# BMS_Slave_v2.net
KiCad netlist of a schematic drawn in EAGLE
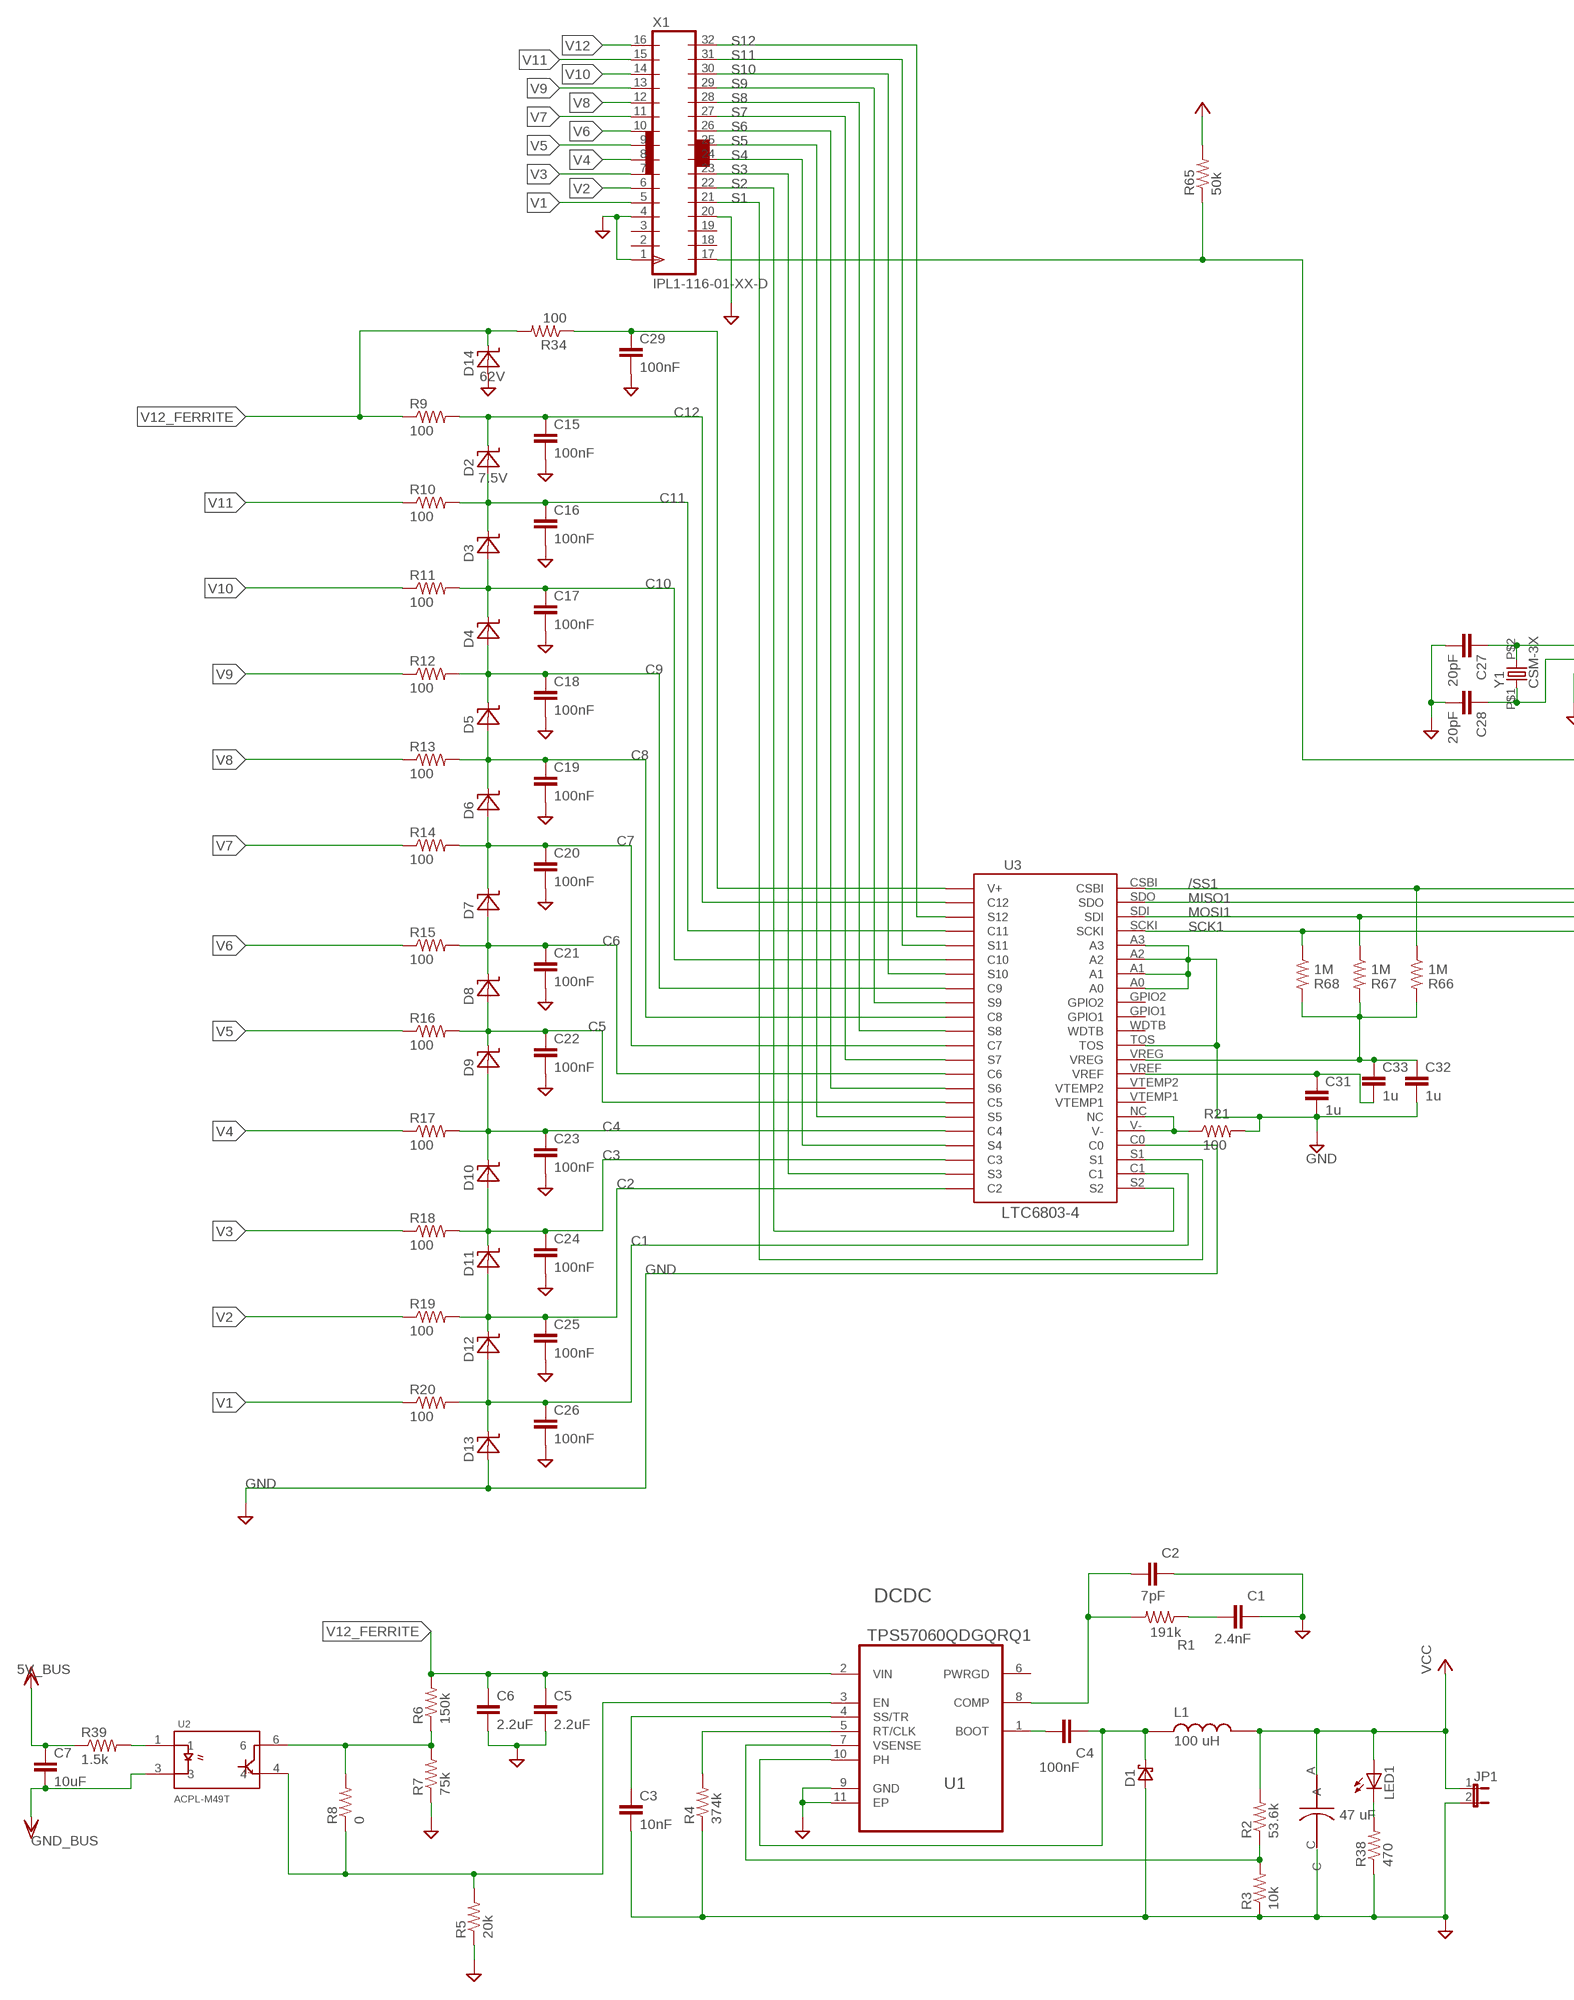
[diagram p0: schematic, sheet 1, part 1 of 2]
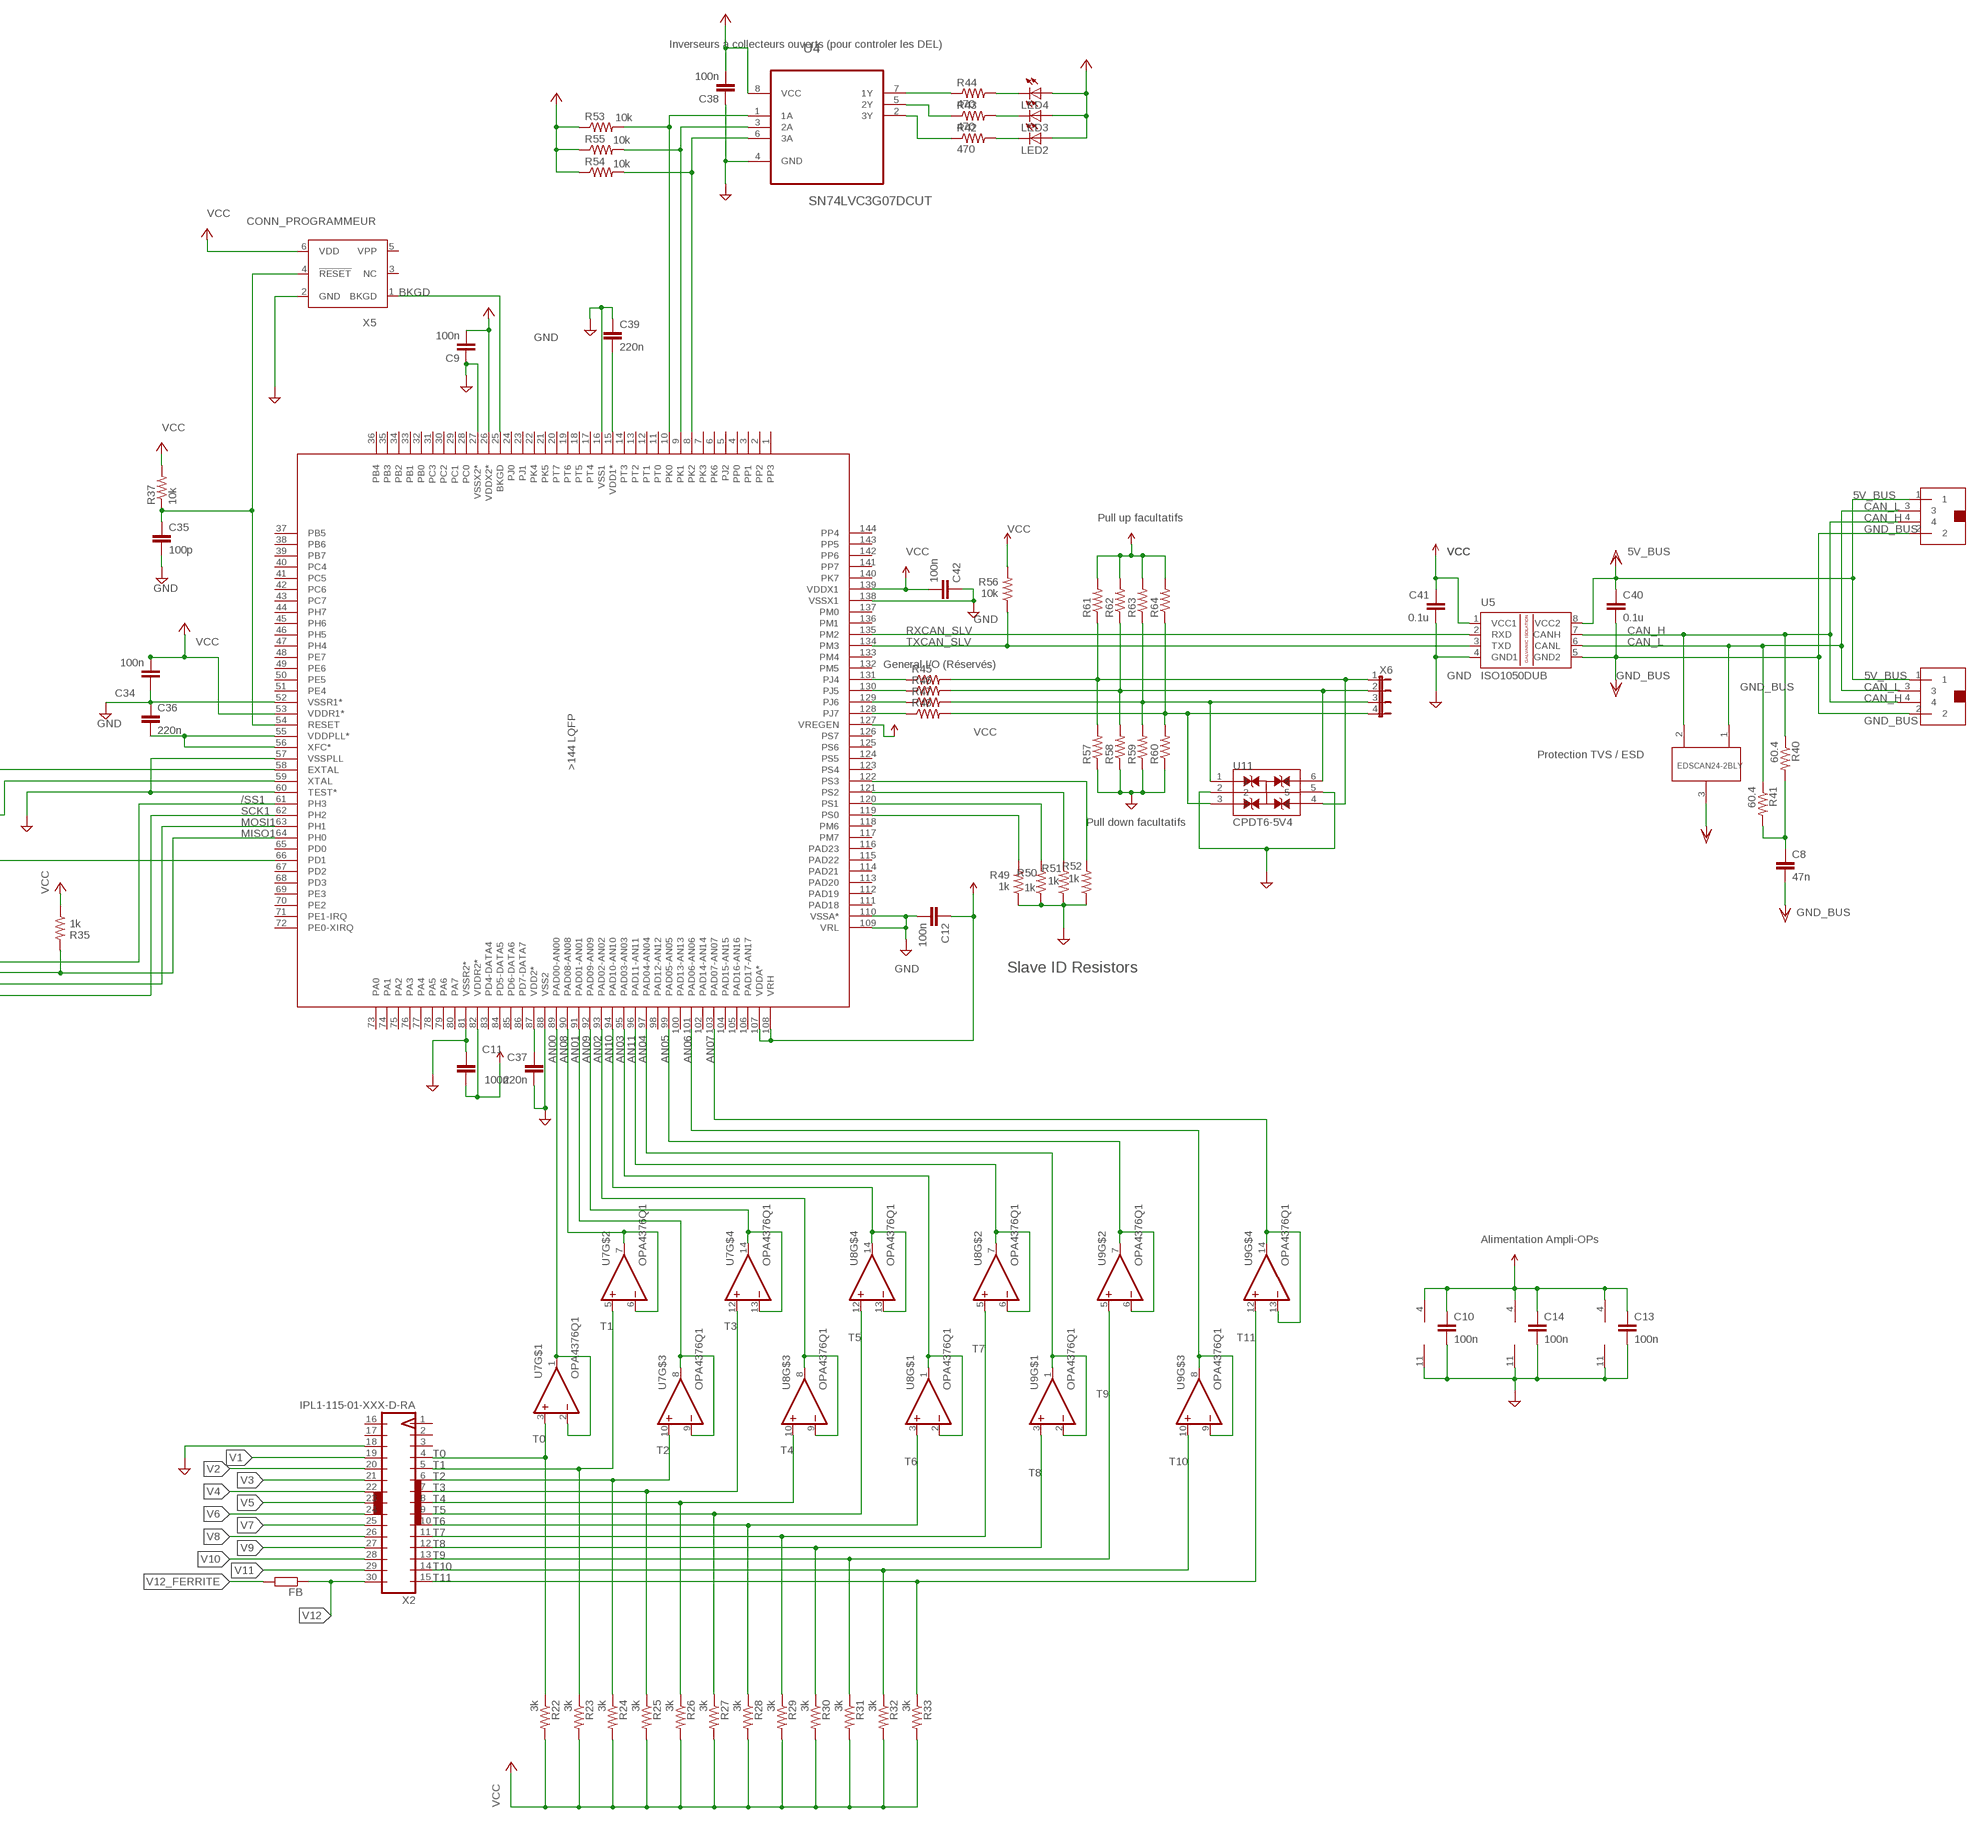
[diagram p1: schematic, sheet 1, part 2 of 2]

(export (version "E")
  (design (tool "Eeschema 10.0.6"))
  (components
    (comp (ref "C1")
      (value "2.4nF")
      (footprint "eagle-import:C0603")
      (libsource (lib "eagle-import") (part "CC0603"))
    )
    (comp (ref "C2")
      (value "7pF")
      (footprint "eagle-import:C0603")
      (libsource (lib "eagle-import") (part "CC0603"))
    )
    (comp (ref "C3")
      (value "10nF")
      (footprint "eagle-import:C0603")
      (libsource (lib "eagle-import") (part "CC0603"))
    )
    (comp (ref "C4")
      (value "100nF")
      (footprint "eagle-import:C0603")
      (libsource (lib "eagle-import") (part "CC0603"))
    )
    (comp (ref "C5")
      (value "2.2uF")
      (footprint "eagle-import:C3225")
      (libsource (lib "eagle-import") (part "resistor_C-EUC3225"))
    )
    (comp (ref "C6")
      (value "2.2uF")
      (footprint "eagle-import:C3225")
      (libsource (lib "eagle-import") (part "resistor_C-EUC3225"))
    )
    (comp (ref "C7")
      (value "10uF")
      (footprint "eagle-import:C0603")
      (libsource (lib "eagle-import") (part "CC0603"))
    )
    (comp (ref "C8")
      (value "47n")
      (footprint "eagle-import:C0603")
      (libsource (lib "eagle-import") (part "C-EUC0603"))
    )
    (comp (ref "C9")
      (value "100n")
      (footprint "eagle-import:C0603")
      (libsource (lib "eagle-import") (part "C-EUC0603"))
    )
    (comp (ref "C10")
      (value "100n")
      (footprint "eagle-import:C0603")
      (libsource (lib "eagle-import") (part "C-EUC0603"))
    )
    (comp (ref "C11")
      (value "100n")
      (footprint "eagle-import:C0603")
      (libsource (lib "eagle-import") (part "CC0603"))
    )
    (comp (ref "C12")
      (value "100n")
      (footprint "eagle-import:C0603")
      (libsource (lib "eagle-import") (part "C-EUC0603"))
    )
    (comp (ref "C13")
      (value "100n")
      (footprint "eagle-import:C0603")
      (libsource (lib "eagle-import") (part "C-EUC0603"))
    )
    (comp (ref "C14")
      (value "100n")
      (footprint "eagle-import:C0603")
      (libsource (lib "eagle-import") (part "C-EUC0603"))
    )
    (comp (ref "C15")
      (value "100nF")
      (footprint "eagle-import:C0603")
      (libsource (lib "eagle-import") (part "CC0603"))
    )
    (comp (ref "C16")
      (value "100nF")
      (footprint "eagle-import:C0603")
      (libsource (lib "eagle-import") (part "CC0603"))
    )
    (comp (ref "C17")
      (value "100nF")
      (footprint "eagle-import:C0603")
      (libsource (lib "eagle-import") (part "CC0603"))
    )
    (comp (ref "C18")
      (value "100nF")
      (footprint "eagle-import:C0603")
      (libsource (lib "eagle-import") (part "CC0603"))
    )
    (comp (ref "C19")
      (value "100nF")
      (footprint "eagle-import:C0603")
      (libsource (lib "eagle-import") (part "CC0603"))
    )
    (comp (ref "C20")
      (value "100nF")
      (footprint "eagle-import:C0603")
      (libsource (lib "eagle-import") (part "CC0603"))
    )
    (comp (ref "C21")
      (value "100nF")
      (footprint "eagle-import:C0603")
      (libsource (lib "eagle-import") (part "CC0603"))
    )
    (comp (ref "C22")
      (value "100nF")
      (footprint "eagle-import:C0603")
      (libsource (lib "eagle-import") (part "CC0603"))
    )
    (comp (ref "C23")
      (value "100nF")
      (footprint "eagle-import:C0603")
      (libsource (lib "eagle-import") (part "CC0603"))
    )
    (comp (ref "C24")
      (value "100nF")
      (footprint "eagle-import:C0603")
      (libsource (lib "eagle-import") (part "CC0603"))
    )
    (comp (ref "C25")
      (value "100nF")
      (footprint "eagle-import:C0603")
      (libsource (lib "eagle-import") (part "CC0603"))
    )
    (comp (ref "C26")
      (value "100nF")
      (footprint "eagle-import:C0603")
      (libsource (lib "eagle-import") (part "CC0603"))
    )
    (comp (ref "C27")
      (value "20pF")
      (footprint "eagle-import:C0603")
      (libsource (lib "eagle-import") (part "C-EUC0603"))
    )
    (comp (ref "C28")
      (value "20pF")
      (footprint "eagle-import:C0603")
      (libsource (lib "eagle-import") (part "C-EUC0603"))
    )
    (comp (ref "C29")
      (value "100nF")
      (footprint "eagle-import:C0603")
      (libsource (lib "eagle-import") (part "CC0603"))
    )
    (comp (ref "C31")
      (value "1u")
      (footprint "eagle-import:C0603")
      (libsource (lib "eagle-import") (part "CC0603"))
    )
    (comp (ref "C32")
      (value "1u")
      (footprint "eagle-import:C0603")
      (libsource (lib "eagle-import") (part "CC0603"))
    )
    (comp (ref "C33")
      (value "1u")
      (footprint "eagle-import:C0603")
      (libsource (lib "eagle-import") (part "CC0603"))
    )
    (comp (ref "C34")
      (value "100n")
      (footprint "eagle-import:C0603")
      (libsource (lib "eagle-import") (part "CC0603"))
    )
    (comp (ref "C35")
      (value "100p")
      (footprint "eagle-import:C0603")
      (libsource (lib "eagle-import") (part "CC0603"))
    )
    (comp (ref "C36")
      (value "220n")
      (footprint "eagle-import:C0603")
      (libsource (lib "eagle-import") (part "CC0603"))
    )
    (comp (ref "C37")
      (value "220n")
      (footprint "eagle-import:C0603")
      (libsource (lib "eagle-import") (part "C-EUC0603"))
    )
    (comp (ref "C38")
      (value "100n")
      (footprint "eagle-import:C0603")
      (libsource (lib "eagle-import") (part "C-EUC0603"))
    )
    (comp (ref "C39")
      (value "220n")
      (footprint "eagle-import:C0603")
      (libsource (lib "eagle-import") (part "C-EUC0603"))
    )
    (comp (ref "C40")
      (value "0.1u")
      (footprint "eagle-import:C0603")
      (libsource (lib "eagle-import") (part "C-EUC0603"))
    )
    (comp (ref "C41")
      (value "0.1u")
      (footprint "eagle-import:C0603")
      (libsource (lib "eagle-import") (part "C-EUC0603"))
    )
    (comp (ref "C42")
      (value "100n")
      (footprint "eagle-import:C0603")
      (libsource (lib "eagle-import") (part "C-EUC0603"))
    )
    (comp (ref "C43")
      (value "47 uF")
      (footprint "eagle-import:APXE_CONDENSATEUR")
      (libsource (lib "eagle-import") (part "APXE_47_COND"))
    )
    (comp (ref "D1")
      (value "BYS12-90GENERIC")
      (footprint "eagle-import:DO214AC_ZENER")
      (libsource (lib "eagle-import") (part "BYS12-90GENERIC"))
    )
    (comp (ref "D2")
      (value "DIODE_ZENER")
      (footprint "eagle-import:SOD123")
      (libsource (lib "eagle-import") (part "DIODE_ZENER"))
    )
    (comp (ref "D3")
      (value "DIODE_ZENER")
      (footprint "eagle-import:SOD123")
      (libsource (lib "eagle-import") (part "DIODE_ZENER"))
    )
    (comp (ref "D4")
      (value "DIODE_ZENER")
      (footprint "eagle-import:SOD123")
      (libsource (lib "eagle-import") (part "DIODE_ZENER"))
    )
    (comp (ref "D5")
      (value "DIODE_ZENER")
      (footprint "eagle-import:SOD123")
      (libsource (lib "eagle-import") (part "DIODE_ZENER"))
    )
    (comp (ref "D6")
      (value "DIODE_ZENER")
      (footprint "eagle-import:SOD123")
      (libsource (lib "eagle-import") (part "DIODE_ZENER"))
    )
    (comp (ref "D7")
      (value "DIODE_ZENER")
      (footprint "eagle-import:SOD123")
      (libsource (lib "eagle-import") (part "DIODE_ZENER"))
    )
    (comp (ref "D8")
      (value "DIODE_ZENER")
      (footprint "eagle-import:SOD123")
      (libsource (lib "eagle-import") (part "DIODE_ZENER"))
    )
    (comp (ref "D9")
      (value "DIODE_ZENER")
      (footprint "eagle-import:SOD123")
      (libsource (lib "eagle-import") (part "DIODE_ZENER"))
    )
    (comp (ref "D10")
      (value "DIODE_ZENER")
      (footprint "eagle-import:SOD123")
      (libsource (lib "eagle-import") (part "DIODE_ZENER"))
    )
    (comp (ref "D11")
      (value "DIODE_ZENER")
      (footprint "eagle-import:SOD123")
      (libsource (lib "eagle-import") (part "DIODE_ZENER"))
    )
    (comp (ref "D12")
      (value "DIODE_ZENER")
      (footprint "eagle-import:SOD123")
      (libsource (lib "eagle-import") (part "DIODE_ZENER"))
    )
    (comp (ref "D13")
      (value "DIODE_ZENER")
      (footprint "eagle-import:SOD123")
      (libsource (lib "eagle-import") (part "DIODE_ZENER"))
    )
    (comp (ref "D14")
      (value "DIODE_ZENER")
      (footprint "eagle-import:SOD123")
      (libsource (lib "eagle-import") (part "DIODE_ZENER"))
    )
    (comp (ref "FB")
      (value "R-EU_R0805")
      (footprint "eagle-import:R0805")
      (libsource (lib "eagle-import") (part "R-EU_R0805"))
    )
    (comp (ref "JP1")
      (value "JP1E")
      (footprint "eagle-import:JP1")
      (libsource (lib "eagle-import") (part "JP1E"))
    )
    (comp (ref "L1")
      (value "100 uH")
      (footprint "eagle-import:VLP8040T-101M")
      (libsource (lib "eagle-import") (part "VLP8040T-101M"))
    )
    (comp (ref "LED1")
      (value "LED")
      (footprint "eagle-import:1206_LED")
      (libsource (lib "eagle-import") (part "LED"))
    )
    (comp (ref "LED2")
      (value "LED")
      (footprint "eagle-import:1206_LED")
      (libsource (lib "eagle-import") (part "ELE4000_BMS_LED"))
    )
    (comp (ref "LED3")
      (value "LED")
      (footprint "eagle-import:1206_LED")
      (libsource (lib "eagle-import") (part "ELE4000_BMS_LED"))
    )
    (comp (ref "LED4")
      (value "LED")
      (footprint "eagle-import:1206_LED")
      (libsource (lib "eagle-import") (part "ELE4000_BMS_LED"))
    )
    (comp (ref "R1")
      (value "191k")
      (footprint "eagle-import:R0603")
      (libsource (lib "eagle-import") (part "resistor_R-US_R0603"))
    )
    (comp (ref "R2")
      (value "53.6k")
      (footprint "eagle-import:R0603")
      (libsource (lib "eagle-import") (part "resistor_R-US_R0603"))
    )
    (comp (ref "R3")
      (value "10k")
      (footprint "eagle-import:R0603")
      (libsource (lib "eagle-import") (part "resistor_R-US_R0603"))
    )
    (comp (ref "R4")
      (value "374k")
      (footprint "eagle-import:R0603")
      (libsource (lib "eagle-import") (part "resistor_R-US_R0603"))
    )
    (comp (ref "R5")
      (value "20k")
      (footprint "eagle-import:R0603")
      (libsource (lib "eagle-import") (part "resistor_R-US_R0603"))
    )
    (comp (ref "R6")
      (value "150k")
      (footprint "eagle-import:R0603")
      (libsource (lib "eagle-import") (part "resistor_R-US_R0603"))
    )
    (comp (ref "R7")
      (value "75k")
      (footprint "eagle-import:R0603")
      (libsource (lib "eagle-import") (part "resistor_R-US_R0603"))
    )
    (comp (ref "R8")
      (value "0")
      (footprint "eagle-import:R0603")
      (libsource (lib "eagle-import") (part "resistor_R-US_R0603"))
    )
    (comp (ref "R9")
      (value "100")
      (footprint "eagle-import:R0603")
      (libsource (lib "eagle-import") (part "resistor_R-US_R0603"))
    )
    (comp (ref "R10")
      (value "100")
      (footprint "eagle-import:R0603")
      (libsource (lib "eagle-import") (part "resistor_R-US_R0603"))
    )
    (comp (ref "R11")
      (value "100")
      (footprint "eagle-import:R0603")
      (libsource (lib "eagle-import") (part "resistor_R-US_R0603"))
    )
    (comp (ref "R12")
      (value "100")
      (footprint "eagle-import:R0603")
      (libsource (lib "eagle-import") (part "resistor_R-US_R0603"))
    )
    (comp (ref "R13")
      (value "100")
      (footprint "eagle-import:R0603")
      (libsource (lib "eagle-import") (part "resistor_R-US_R0603"))
    )
    (comp (ref "R14")
      (value "100")
      (footprint "eagle-import:R0603")
      (libsource (lib "eagle-import") (part "resistor_R-US_R0603"))
    )
    (comp (ref "R15")
      (value "100")
      (footprint "eagle-import:R0603")
      (libsource (lib "eagle-import") (part "resistor_R-US_R0603"))
    )
    (comp (ref "R16")
      (value "100")
      (footprint "eagle-import:R0603")
      (libsource (lib "eagle-import") (part "resistor_R-US_R0603"))
    )
    (comp (ref "R17")
      (value "100")
      (footprint "eagle-import:R0603")
      (libsource (lib "eagle-import") (part "resistor_R-US_R0603"))
    )
    (comp (ref "R18")
      (value "100")
      (footprint "eagle-import:R0603")
      (libsource (lib "eagle-import") (part "resistor_R-US_R0603"))
    )
    (comp (ref "R19")
      (value "100")
      (footprint "eagle-import:R0603")
      (libsource (lib "eagle-import") (part "resistor_R-US_R0603"))
    )
    (comp (ref "R20")
      (value "100")
      (footprint "eagle-import:R0603")
      (libsource (lib "eagle-import") (part "resistor_R-US_R0603"))
    )
    (comp (ref "R21")
      (value "100")
      (footprint "eagle-import:R0603")
      (libsource (lib "eagle-import") (part "resistor_R-US_R0603"))
    )
    (comp (ref "R22")
      (value "3k")
      (footprint "eagle-import:R0603")
      (libsource (lib "eagle-import") (part "R-US_R0603"))
    )
    (comp (ref "R23")
      (value "3k")
      (footprint "eagle-import:R0603")
      (libsource (lib "eagle-import") (part "R-US_R0603"))
    )
    (comp (ref "R24")
      (value "3k")
      (footprint "eagle-import:R0603")
      (libsource (lib "eagle-import") (part "R-US_R0603"))
    )
    (comp (ref "R25")
      (value "3k")
      (footprint "eagle-import:R0603")
      (libsource (lib "eagle-import") (part "R-US_R0603"))
    )
    (comp (ref "R26")
      (value "3k")
      (footprint "eagle-import:R0603")
      (libsource (lib "eagle-import") (part "R-US_R0603"))
    )
    (comp (ref "R27")
      (value "3k")
      (footprint "eagle-import:R0603")
      (libsource (lib "eagle-import") (part "R-US_R0603"))
    )
    (comp (ref "R28")
      (value "3k")
      (footprint "eagle-import:R0603")
      (libsource (lib "eagle-import") (part "R-US_R0603"))
    )
    (comp (ref "R29")
      (value "3k")
      (footprint "eagle-import:R0603")
      (libsource (lib "eagle-import") (part "R-US_R0603"))
    )
    (comp (ref "R30")
      (value "3k")
      (footprint "eagle-import:R0603")
      (libsource (lib "eagle-import") (part "R-US_R0603"))
    )
    (comp (ref "R31")
      (value "3k")
      (footprint "eagle-import:R0603")
      (libsource (lib "eagle-import") (part "R-US_R0603"))
    )
    (comp (ref "R32")
      (value "3k")
      (footprint "eagle-import:R0603")
      (libsource (lib "eagle-import") (part "R-US_R0603"))
    )
    (comp (ref "R33")
      (value "3k")
      (footprint "eagle-import:R0603")
      (libsource (lib "eagle-import") (part "R-US_R0603"))
    )
    (comp (ref "R34")
      (value "100")
      (footprint "eagle-import:R0603")
      (libsource (lib "eagle-import") (part "resistor_R-US_R0603"))
    )
    (comp (ref "R35")
      (value "1k")
      (footprint "eagle-import:R0603")
      (libsource (lib "eagle-import") (part "resistor_R-US_R0603"))
    )
    (comp (ref "R37")
      (value "10k")
      (footprint "eagle-import:R0603")
      (libsource (lib "eagle-import") (part "resistor_R-US_R0603"))
    )
    (comp (ref "R38")
      (value "470")
      (footprint "eagle-import:R0603")
      (libsource (lib "eagle-import") (part "R-US_R0603"))
    )
    (comp (ref "R39")
      (value "1.5k")
      (footprint "eagle-import:R0603")
      (libsource (lib "eagle-import") (part "resistor_R-US_R0603"))
    )
    (comp (ref "R40")
      (value "60.4")
      (footprint "eagle-import:R0603")
      (libsource (lib "eagle-import") (part "R-US_R0603"))
    )
    (comp (ref "R41")
      (value "60.4")
      (footprint "eagle-import:R0603")
      (libsource (lib "eagle-import") (part "R-US_R0603"))
    )
    (comp (ref "R42")
      (value "470")
      (footprint "eagle-import:R0603")
      (libsource (lib "eagle-import") (part "resistor_R-US_R0603"))
    )
    (comp (ref "R43")
      (value "470")
      (footprint "eagle-import:R0603")
      (libsource (lib "eagle-import") (part "resistor_R-US_R0603"))
    )
    (comp (ref "R44")
      (value "470")
      (footprint "eagle-import:R0603")
      (libsource (lib "eagle-import") (part "resistor_R-US_R0603"))
    )
    (comp (ref "R45")
      (value "R-US_R0603")
      (footprint "eagle-import:R0603")
      (libsource (lib "eagle-import") (part "R-US_R0603"))
    )
    (comp (ref "R46")
      (value "R-US_R0603")
      (footprint "eagle-import:R0603")
      (libsource (lib "eagle-import") (part "R-US_R0603"))
    )
    (comp (ref "R47")
      (value "R-US_R0603")
      (footprint "eagle-import:R0603")
      (libsource (lib "eagle-import") (part "R-US_R0603"))
    )
    (comp (ref "R48")
      (value "R-US_R0603")
      (footprint "eagle-import:R0603")
      (libsource (lib "eagle-import") (part "R-US_R0603"))
    )
    (comp (ref "R49")
      (value "1k")
      (footprint "eagle-import:R0603")
      (libsource (lib "eagle-import") (part "resistor_R-US_R0603"))
    )
    (comp (ref "R50")
      (value "1k")
      (footprint "eagle-import:R0603")
      (libsource (lib "eagle-import") (part "resistor_R-US_R0603"))
    )
    (comp (ref "R51")
      (value "1k")
      (footprint "eagle-import:R0603")
      (libsource (lib "eagle-import") (part "resistor_R-US_R0603"))
    )
    (comp (ref "R52")
      (value "1k")
      (footprint "eagle-import:R0603")
      (libsource (lib "eagle-import") (part "resistor_R-US_R0603"))
    )
    (comp (ref "R53")
      (value "10k")
      (footprint "eagle-import:R0603")
      (libsource (lib "eagle-import") (part "resistor_R-US_R0603"))
    )
    (comp (ref "R54")
      (value "10k")
      (footprint "eagle-import:R0603")
      (libsource (lib "eagle-import") (part "resistor_R-US_R0603"))
    )
    (comp (ref "R55")
      (value "10k")
      (footprint "eagle-import:R0603")
      (libsource (lib "eagle-import") (part "resistor_R-US_R0603"))
    )
    (comp (ref "R56")
      (value "10k")
      (footprint "eagle-import:R0603")
      (libsource (lib "eagle-import") (part "resistor_R-US_R0603"))
    )
    (comp (ref "R57")
      (value "R-US_R0603")
      (footprint "eagle-import:R0603")
      (libsource (lib "eagle-import") (part "R-US_R0603"))
    )
    (comp (ref "R58")
      (value "R-US_R0603")
      (footprint "eagle-import:R0603")
      (libsource (lib "eagle-import") (part "R-US_R0603"))
    )
    (comp (ref "R59")
      (value "R-US_R0603")
      (footprint "eagle-import:R0603")
      (libsource (lib "eagle-import") (part "R-US_R0603"))
    )
    (comp (ref "R60")
      (value "R-US_R0603")
      (footprint "eagle-import:R0603")
      (libsource (lib "eagle-import") (part "R-US_R0603"))
    )
    (comp (ref "R61")
      (value "R-US_R0603")
      (footprint "eagle-import:R0603")
      (libsource (lib "eagle-import") (part "R-US_R0603"))
    )
    (comp (ref "R62")
      (value "R-US_R0603")
      (footprint "eagle-import:R0603")
      (libsource (lib "eagle-import") (part "R-US_R0603"))
    )
    (comp (ref "R63")
      (value "R-US_R0603")
      (footprint "eagle-import:R0603")
      (libsource (lib "eagle-import") (part "R-US_R0603"))
    )
    (comp (ref "R64")
      (value "R-US_R0603")
      (footprint "eagle-import:R0603")
      (libsource (lib "eagle-import") (part "R-US_R0603"))
    )
    (comp (ref "R65")
      (value "50k")
      (footprint "eagle-import:R0603")
      (libsource (lib "eagle-import") (part "resistor_R-US_R0603"))
    )
    (comp (ref "R66")
      (value "1M")
      (footprint "eagle-import:R0603")
      (libsource (lib "eagle-import") (part "resistor_R-US_R0603"))
    )
    (comp (ref "R67")
      (value "1M")
      (footprint "eagle-import:R0603")
      (libsource (lib "eagle-import") (part "resistor_R-US_R0603"))
    )
    (comp (ref "R68")
      (value "1M")
      (footprint "eagle-import:R0603")
      (libsource (lib "eagle-import") (part "resistor_R-US_R0603"))
    )
    (comp (ref "U1")
      (value "TPS57060QDGQRQ1")
      (footprint "eagle-import:SOP50P490X110-11N")
      (fields (field (name "MPN") "TPS54060QDGQRQ1"))
      (libsource (lib "eagle-import") (part "TPS54060QDGQRQ1"))
    )
    (comp (ref "U2")
      (value "ACPL-M49T")
      (footprint "eagle-import:SO5")
      (libsource (lib "eagle-import") (part "ACPL-M49T"))
    )
    (comp (ref "U3")
      (value "LTC6803-4")
      (footprint "eagle-import:LTC6803-4")
      (libsource (lib "eagle-import") (part "LTC6803-4"))
    )
    (comp (ref "U4")
      (value "SN74LVC3G07DCUT")
      (footprint "eagle-import:SOP50P310X90-8N")
      (libsource (lib "eagle-import") (part "SN74LVC3G07DCUT"))
    )
    (comp (ref "U5")
      (value "ISO1050DUB")
      (footprint "eagle-import:DUB-R-PDSO-G8")
      (fields (field (name "MPN") "ISO1050DUBR"))
      (libsource (lib "eagle-import") (part "ISO1050DUB"))
    )
    (comp (ref "U6")
      (value "MC9S12XD-144")
      (footprint "eagle-import:SQFP-S-20X20-144")
      (fields (field (name "MPN") "LFDAS12XFLT"))
      (libsource (lib "eagle-import") (part "MC9S12XD-144"))
    )
    (comp (ref "U7")
      (value "OPA4376Q1")
      (footprint "eagle-import:TSSOP-14")
      (libsource (lib "eagle-import") (part "OPA4376Q1"))
    )
    (comp (ref "U8")
      (value "OPA4376Q1")
      (footprint "eagle-import:TSSOP-14")
      (libsource (lib "eagle-import") (part "OPA4376Q1"))
    )
    (comp (ref "U9")
      (value "OPA4376Q1")
      (footprint "eagle-import:TSSOP-14")
      (libsource (lib "eagle-import") (part "OPA4376Q1"))
    )
    (comp (ref "U10")
      (value "EDSCAN24-2BLY")
      (footprint "eagle-import:SOT23-3")
      (libsource (lib "eagle-import") (part "EDSCAN24-2BLY"))
    )
    (comp (ref "U11")
      (value "CPDT6-5V4")
      (footprint "eagle-import:SOT23-6")
      (libsource (lib "eagle-import") (part "CPDT6-5V4"))
    )
    (comp (ref "X1")
      (value "IPL1-116-01-XX-D")
      (footprint "eagle-import:IPL1-116-01-XX-D")
      (libsource (lib "eagle-import") (part "IPL1-116-01-XX-D"))
    )
    (comp (ref "X2")
      (value "IPL1-115-01-XXX-D-RA")
      (footprint "eagle-import:IPL1-115-01-XXX-D-RA")
      (libsource (lib "eagle-import") (part "IPL1-115-01-XXX-D-RA"))
    )
    (comp (ref "X3")
      (value "IPL1-102-01-XXX-D-RA")
      (footprint "eagle-import:IPL1-102-01-XXX-D-RA")
      (libsource (lib "eagle-import") (part "IPL1-102-01-XXX-D-RA"))
    )
    (comp (ref "X4")
      (value "IPL1-102-01-XXX-D-RA")
      (footprint "eagle-import:IPL1-102-01-XXX-D-RA")
      (libsource (lib "eagle-import") (part "IPL1-102-01-XXX-D-RA"))
    )
    (comp (ref "X5")
      (value "CONN_PROGRAMMEUR")
      (footprint "eagle-import:CONNECTEUR_PROGRAMMEUR")
      (libsource (lib "eagle-import") (part "CONN_PROGRAMMEUR"))
    )
    (comp (ref "X6")
      (value "JP4E")
      (footprint "eagle-import:JP4")
      (libsource (lib "eagle-import") (part "JP4E"))
    )
    (comp (ref "Y1")
      (value "CSM-3X")
      (footprint "eagle-import:CSM-3X")
      (libsource (lib "eagle-import") (part "CSM-3X"))
    )
  )
  (nets
    (net (code "1") (name "/AN00") (class "Default")
      (node (ref "U6") (pin "89") (pinfunction "PAD00-AN00_89") (pintype "bidirectional"))
      (node (ref "U7") (pin "1") (pinfunction "OUT_1") (pintype "output"))
      (node (ref "U7") (pin "2") (pinfunction "-IN_2") (pintype "input"))
    )
    (net (code "2") (name "/AN01") (class "Default")
      (node (ref "U6") (pin "91") (pinfunction "PAD01-AN01_91") (pintype "bidirectional"))
      (node (ref "U7") (pin "8") (pinfunction "OUT_8") (pintype "output"))
      (node (ref "U7") (pin "9") (pinfunction "-IN_9") (pintype "input"))
    )
    (net (code "3") (name "/AN02") (class "Default")
      (node (ref "U6") (pin "93") (pinfunction "PAD02-AN02_93") (pintype "bidirectional"))
      (node (ref "U8") (pin "8") (pinfunction "OUT_8") (pintype "output"))
      (node (ref "U8") (pin "9") (pinfunction "-IN_9") (pintype "input"))
    )
    (net (code "4") (name "/AN03") (class "Default")
      (node (ref "U6") (pin "95") (pinfunction "PAD03-AN03_95") (pintype "bidirectional"))
      (node (ref "U8") (pin "1") (pinfunction "OUT_1") (pintype "output"))
      (node (ref "U8") (pin "2") (pinfunction "-IN_2") (pintype "input"))
    )
    (net (code "5") (name "/AN04") (class "Default")
      (node (ref "U6") (pin "97") (pinfunction "PAD04-AN04_97") (pintype "bidirectional"))
      (node (ref "U9") (pin "1") (pinfunction "OUT_1") (pintype "output"))
      (node (ref "U9") (pin "2") (pinfunction "-IN_2") (pintype "input"))
    )
    (net (code "6") (name "/AN05") (class "Default")
      (node (ref "U6") (pin "99") (pinfunction "PAD05-AN05_99") (pintype "bidirectional"))
      (node (ref "U9") (pin "6") (pinfunction "-IN_6") (pintype "input"))
      (node (ref "U9") (pin "7") (pinfunction "OUT_7") (pintype "output"))
    )
    (net (code "7") (name "/AN06") (class "Default")
      (node (ref "U6") (pin "101") (pinfunction "PAD06-AN06_101") (pintype "bidirectional"))
      (node (ref "U9") (pin "8") (pinfunction "OUT_8") (pintype "output"))
      (node (ref "U9") (pin "9") (pinfunction "-IN_9") (pintype "input"))
    )
    (net (code "8") (name "/AN07") (class "Default")
      (node (ref "U6") (pin "103") (pinfunction "PAD07-AN07_103") (pintype "bidirectional"))
      (node (ref "U9") (pin "13") (pinfunction "-IN_13") (pintype "input"))
      (node (ref "U9") (pin "14") (pinfunction "OUT_14") (pintype "output"))
    )
    (net (code "9") (name "/AN08") (class "Default")
      (node (ref "U6") (pin "90") (pinfunction "PAD08-AN08_90") (pintype "bidirectional"))
      (node (ref "U7") (pin "6") (pinfunction "-IN_6") (pintype "input"))
      (node (ref "U7") (pin "7") (pinfunction "OUT_7") (pintype "output"))
    )
    (net (code "10") (name "/AN09") (class "Default")
      (node (ref "U6") (pin "92") (pinfunction "PAD09-AN09_92") (pintype "bidirectional"))
      (node (ref "U7") (pin "13") (pinfunction "-IN_13") (pintype "input"))
      (node (ref "U7") (pin "14") (pinfunction "OUT_14") (pintype "output"))
    )
    (net (code "11") (name "/AN10") (class "Default")
      (node (ref "U6") (pin "94") (pinfunction "PAD10-AN10_94") (pintype "bidirectional"))
      (node (ref "U8") (pin "13") (pinfunction "-IN_13") (pintype "input"))
      (node (ref "U8") (pin "14") (pinfunction "OUT_14") (pintype "output"))
    )
    (net (code "12") (name "/AN11") (class "Default")
      (node (ref "U6") (pin "96") (pinfunction "PAD11-AN11_96") (pintype "bidirectional"))
      (node (ref "U8") (pin "6") (pinfunction "-IN_6") (pintype "input"))
      (node (ref "U8") (pin "7") (pinfunction "OUT_7") (pintype "output"))
    )
    (net (code "13") (name "/BKGD") (class "Default")
      (node (ref "U6") (pin "25") (pinfunction "BKGD_25") (pintype "bidirectional"))
      (node (ref "X5") (pin "1") (pinfunction "BKGD_1") (pintype "bidirectional"))
    )
    (net (code "14") (name "/C1") (class "Default")
      (node (ref "C26") (pin "1") (pinfunction "1_1") (pintype "passive"))
      (node (ref "D12") (pin "A") (pinfunction "A_A") (pintype "passive"))
      (node (ref "D13") (pin "C") (pinfunction "C_C") (pintype "passive"))
      (node (ref "R20") (pin "2") (pinfunction "2_2") (pintype "passive"))
      (node (ref "U3") (pin "C1") (pinfunction "C1_C1") (pintype "bidirectional"))
    )
    (net (code "15") (name "/C2") (class "Default")
      (node (ref "C25") (pin "1") (pinfunction "1_1") (pintype "passive"))
      (node (ref "D11") (pin "A") (pinfunction "A_A") (pintype "passive"))
      (node (ref "D12") (pin "C") (pinfunction "C_C") (pintype "passive"))
      (node (ref "R19") (pin "2") (pinfunction "2_2") (pintype "passive"))
      (node (ref "U3") (pin "C2") (pinfunction "C2_C2") (pintype "bidirectional"))
    )
    (net (code "16") (name "/C3") (class "Default")
      (node (ref "C24") (pin "1") (pinfunction "1_1") (pintype "passive"))
      (node (ref "D10") (pin "A") (pinfunction "A_A") (pintype "passive"))
      (node (ref "D11") (pin "C") (pinfunction "C_C") (pintype "passive"))
      (node (ref "R18") (pin "2") (pinfunction "2_2") (pintype "passive"))
      (node (ref "U3") (pin "C3") (pinfunction "C3_C3") (pintype "bidirectional"))
    )
    (net (code "17") (name "/C4") (class "Default")
      (node (ref "C23") (pin "1") (pinfunction "1_1") (pintype "passive"))
      (node (ref "D10") (pin "C") (pinfunction "C_C") (pintype "passive"))
      (node (ref "D9") (pin "A") (pinfunction "A_A") (pintype "passive"))
      (node (ref "R17") (pin "2") (pinfunction "2_2") (pintype "passive"))
      (node (ref "U3") (pin "C4") (pinfunction "C4_C4") (pintype "bidirectional"))
    )
    (net (code "18") (name "/C5") (class "Default")
      (node (ref "C22") (pin "1") (pinfunction "1_1") (pintype "passive"))
      (node (ref "D8") (pin "A") (pinfunction "A_A") (pintype "passive"))
      (node (ref "D9") (pin "C") (pinfunction "C_C") (pintype "passive"))
      (node (ref "R16") (pin "2") (pinfunction "2_2") (pintype "passive"))
      (node (ref "U3") (pin "C5") (pinfunction "C5_C5") (pintype "bidirectional"))
    )
    (net (code "19") (name "/C6") (class "Default")
      (node (ref "C21") (pin "1") (pinfunction "1_1") (pintype "passive"))
      (node (ref "D7") (pin "A") (pinfunction "A_A") (pintype "passive"))
      (node (ref "D8") (pin "C") (pinfunction "C_C") (pintype "passive"))
      (node (ref "R15") (pin "2") (pinfunction "2_2") (pintype "passive"))
      (node (ref "U3") (pin "C6") (pinfunction "C6_C6") (pintype "bidirectional"))
    )
    (net (code "20") (name "/C7") (class "Default")
      (node (ref "C20") (pin "1") (pinfunction "1_1") (pintype "passive"))
      (node (ref "D6") (pin "A") (pinfunction "A_A") (pintype "passive"))
      (node (ref "D7") (pin "C") (pinfunction "C_C") (pintype "passive"))
      (node (ref "R14") (pin "2") (pinfunction "2_2") (pintype "passive"))
      (node (ref "U3") (pin "C7") (pinfunction "C7_C7") (pintype "bidirectional"))
    )
    (net (code "21") (name "/C8") (class "Default")
      (node (ref "C19") (pin "1") (pinfunction "1_1") (pintype "passive"))
      (node (ref "D5") (pin "A") (pinfunction "A_A") (pintype "passive"))
      (node (ref "D6") (pin "C") (pinfunction "C_C") (pintype "passive"))
      (node (ref "R13") (pin "2") (pinfunction "2_2") (pintype "passive"))
      (node (ref "U3") (pin "C8") (pinfunction "C8_C8") (pintype "bidirectional"))
    )
    (net (code "22") (name "/C9") (class "Default")
      (node (ref "C18") (pin "1") (pinfunction "1_1") (pintype "passive"))
      (node (ref "D4") (pin "A") (pinfunction "A_A") (pintype "passive"))
      (node (ref "D5") (pin "C") (pinfunction "C_C") (pintype "passive"))
      (node (ref "R12") (pin "2") (pinfunction "2_2") (pintype "passive"))
      (node (ref "U3") (pin "C9") (pinfunction "C9_C9") (pintype "bidirectional"))
    )
    (net (code "23") (name "/C10") (class "Default")
      (node (ref "C17") (pin "1") (pinfunction "1_1") (pintype "passive"))
      (node (ref "D3") (pin "A") (pinfunction "A_A") (pintype "passive"))
      (node (ref "D4") (pin "C") (pinfunction "C_C") (pintype "passive"))
      (node (ref "R11") (pin "2") (pinfunction "2_2") (pintype "passive"))
      (node (ref "U3") (pin "C10") (pinfunction "C10_C10") (pintype "bidirectional"))
    )
    (net (code "24") (name "/C11") (class "Default")
      (node (ref "C16") (pin "1") (pinfunction "1_1") (pintype "passive"))
      (node (ref "D2") (pin "A") (pinfunction "A_A") (pintype "passive"))
      (node (ref "D3") (pin "C") (pinfunction "C_C") (pintype "passive"))
      (node (ref "R10") (pin "2") (pinfunction "2_2") (pintype "passive"))
      (node (ref "U3") (pin "C11") (pinfunction "C11_C11") (pintype "bidirectional"))
    )
    (net (code "25") (name "/C12") (class "Default")
      (node (ref "C15") (pin "1") (pinfunction "1_1") (pintype "passive"))
      (node (ref "D2") (pin "C") (pinfunction "C_C") (pintype "passive"))
      (node (ref "R9") (pin "2") (pinfunction "2_2") (pintype "passive"))
      (node (ref "U3") (pin "C12") (pinfunction "C12_C12") (pintype "bidirectional"))
    )
    (net (code "26") (name "/CAN_H") (class "Default")
      (node (ref "R40") (pin "1") (pinfunction "1_1") (pintype "passive"))
      (node (ref "U10") (pin "2") (pinfunction "2_2") (pintype "bidirectional"))
      (node (ref "U5") (pin "7") (pinfunction "CANH_7") (pintype "input"))
      (node (ref "X3") (pin "4") (pinfunction "4_4") (pintype "bidirectional"))
      (node (ref "X4") (pin "4") (pinfunction "4_4") (pintype "bidirectional"))
    )
    (net (code "27") (name "/CAN_L") (class "Default")
      (node (ref "R41") (pin "1") (pinfunction "1_1") (pintype "passive"))
      (node (ref "U10") (pin "1") (pinfunction "1_1") (pintype "bidirectional"))
      (node (ref "U5") (pin "6") (pinfunction "CANL_6") (pintype "input"))
      (node (ref "X3") (pin "3") (pinfunction "3_3") (pintype "bidirectional"))
      (node (ref "X4") (pin "3") (pinfunction "3_3") (pintype "bidirectional"))
    )
    (net (code "28") (name "/MISO1") (class "Default")
      (node (ref "R35") (pin "2") (pinfunction "2_2") (pintype "passive"))
      (node (ref "U3") (pin "SDO") (pinfunction "SDO_SDO") (pintype "bidirectional"))
      (node (ref "U6") (pin "64") (pinfunction "PH0_64") (pintype "bidirectional"))
    )
    (net (code "29") (name "/MOSI1") (class "Default")
      (node (ref "R67") (pin "1") (pinfunction "1_1") (pintype "passive"))
      (node (ref "U3") (pin "SDI") (pinfunction "SDI_SDI") (pintype "bidirectional"))
      (node (ref "U6") (pin "63") (pinfunction "PH1_63") (pintype "bidirectional"))
    )
    (net (code "30") (name "/RXCAN_SLV") (class "Default")
      (node (ref "U5") (pin "2") (pinfunction "RXD_2") (pintype "input"))
      (node (ref "U6") (pin "135") (pinfunction "PM2_135") (pintype "bidirectional"))
    )
    (net (code "31") (name "/S1") (class "Default")
      (node (ref "U3") (pin "S1") (pinfunction "S1_S1") (pintype "bidirectional"))
      (node (ref "X1") (pin "21") (pinfunction "21_21") (pintype "bidirectional"))
    )
    (net (code "32") (name "/S2") (class "Default")
      (node (ref "U3") (pin "S2") (pinfunction "S2_S2") (pintype "bidirectional"))
      (node (ref "X1") (pin "22") (pinfunction "22_22") (pintype "bidirectional"))
    )
    (net (code "33") (name "/S3") (class "Default")
      (node (ref "U3") (pin "S3") (pinfunction "S3_S3") (pintype "bidirectional"))
      (node (ref "X1") (pin "23") (pinfunction "23_23") (pintype "bidirectional"))
    )
    (net (code "34") (name "/S4") (class "Default")
      (node (ref "U3") (pin "S4") (pinfunction "S4_S4") (pintype "bidirectional"))
      (node (ref "X1") (pin "24") (pinfunction "24_24") (pintype "bidirectional"))
    )
    (net (code "35") (name "/S5") (class "Default")
      (node (ref "U3") (pin "S5") (pinfunction "S5_S5") (pintype "bidirectional"))
      (node (ref "X1") (pin "25") (pinfunction "25_25") (pintype "bidirectional"))
    )
    (net (code "36") (name "/S6") (class "Default")
      (node (ref "U3") (pin "S6") (pinfunction "S6_S6") (pintype "bidirectional"))
      (node (ref "X1") (pin "26") (pinfunction "26_26") (pintype "bidirectional"))
    )
    (net (code "37") (name "/S7") (class "Default")
      (node (ref "U3") (pin "S7") (pinfunction "S7_S7") (pintype "bidirectional"))
      (node (ref "X1") (pin "27") (pinfunction "27_27") (pintype "bidirectional"))
    )
    (net (code "38") (name "/S8") (class "Default")
      (node (ref "U3") (pin "S8") (pinfunction "S8_S8") (pintype "bidirectional"))
      (node (ref "X1") (pin "28") (pinfunction "28_28") (pintype "bidirectional"))
    )
    (net (code "39") (name "/S9") (class "Default")
      (node (ref "U3") (pin "S9") (pinfunction "S9_S9") (pintype "bidirectional"))
      (node (ref "X1") (pin "29") (pinfunction "29_29") (pintype "bidirectional"))
    )
    (net (code "40") (name "/S10") (class "Default")
      (node (ref "U3") (pin "S10") (pinfunction "S10_S10") (pintype "bidirectional"))
      (node (ref "X1") (pin "30") (pinfunction "30_30") (pintype "bidirectional"))
    )
    (net (code "41") (name "/S11") (class "Default")
      (node (ref "U3") (pin "S11") (pinfunction "S11_S11") (pintype "bidirectional"))
      (node (ref "X1") (pin "31") (pinfunction "31_31") (pintype "bidirectional"))
    )
    (net (code "42") (name "/S12") (class "Default")
      (node (ref "U3") (pin "S12") (pinfunction "S12_S12") (pintype "bidirectional"))
      (node (ref "X1") (pin "32") (pinfunction "32_32") (pintype "bidirectional"))
    )
    (net (code "43") (name "/SCK1") (class "Default")
      (node (ref "R68") (pin "1") (pinfunction "1_1") (pintype "passive"))
      (node (ref "U3") (pin "SCKI") (pinfunction "SCKI_SCKI") (pintype "bidirectional"))
      (node (ref "U6") (pin "62") (pinfunction "PH2_62") (pintype "bidirectional"))
    )
    (net (code "44") (name "/T0") (class "Default")
      (node (ref "R22") (pin "1") (pinfunction "1_1") (pintype "passive"))
      (node (ref "U7") (pin "3") (pinfunction "+IN_3") (pintype "input"))
      (node (ref "X2") (pin "4") (pinfunction "4_4") (pintype "bidirectional"))
    )
    (net (code "45") (name "/T1") (class "Default")
      (node (ref "R23") (pin "1") (pinfunction "1_1") (pintype "passive"))
      (node (ref "U7") (pin "5") (pinfunction "+IN_5") (pintype "input"))
      (node (ref "X2") (pin "5") (pinfunction "5_5") (pintype "bidirectional"))
    )
    (net (code "46") (name "/T2") (class "Default")
      (node (ref "R24") (pin "1") (pinfunction "1_1") (pintype "passive"))
      (node (ref "U7") (pin "10") (pinfunction "+IN_10") (pintype "input"))
      (node (ref "X2") (pin "6") (pinfunction "6_6") (pintype "bidirectional"))
    )
    (net (code "47") (name "/T3") (class "Default")
      (node (ref "R25") (pin "1") (pinfunction "1_1") (pintype "passive"))
      (node (ref "U7") (pin "12") (pinfunction "+IN_12") (pintype "input"))
      (node (ref "X2") (pin "7") (pinfunction "7_7") (pintype "bidirectional"))
    )
    (net (code "48") (name "/T4") (class "Default")
      (node (ref "R26") (pin "1") (pinfunction "1_1") (pintype "passive"))
      (node (ref "U8") (pin "10") (pinfunction "+IN_10") (pintype "input"))
      (node (ref "X2") (pin "8") (pinfunction "8_8") (pintype "bidirectional"))
    )
    (net (code "49") (name "/T5") (class "Default")
      (node (ref "R27") (pin "1") (pinfunction "1_1") (pintype "passive"))
      (node (ref "U8") (pin "12") (pinfunction "+IN_12") (pintype "input"))
      (node (ref "X2") (pin "9") (pinfunction "9_9") (pintype "bidirectional"))
    )
    (net (code "50") (name "/T6") (class "Default")
      (node (ref "R28") (pin "1") (pinfunction "1_1") (pintype "passive"))
      (node (ref "U8") (pin "3") (pinfunction "+IN_3") (pintype "input"))
      (node (ref "X2") (pin "10") (pinfunction "10_10") (pintype "bidirectional"))
    )
    (net (code "51") (name "/T7") (class "Default")
      (node (ref "R29") (pin "1") (pinfunction "1_1") (pintype "passive"))
      (node (ref "U8") (pin "5") (pinfunction "+IN_5") (pintype "input"))
      (node (ref "X2") (pin "11") (pinfunction "11_11") (pintype "bidirectional"))
    )
    (net (code "52") (name "/T8") (class "Default")
      (node (ref "R30") (pin "1") (pinfunction "1_1") (pintype "passive"))
      (node (ref "U9") (pin "3") (pinfunction "+IN_3") (pintype "input"))
      (node (ref "X2") (pin "12") (pinfunction "12_12") (pintype "bidirectional"))
    )
    (net (code "53") (name "/T9") (class "Default")
      (node (ref "R31") (pin "1") (pinfunction "1_1") (pintype "passive"))
      (node (ref "U9") (pin "5") (pinfunction "+IN_5") (pintype "input"))
      (node (ref "X2") (pin "13") (pinfunction "13_13") (pintype "bidirectional"))
    )
    (net (code "54") (name "/T10") (class "Default")
      (node (ref "R32") (pin "1") (pinfunction "1_1") (pintype "passive"))
      (node (ref "U9") (pin "10") (pinfunction "+IN_10") (pintype "input"))
      (node (ref "X2") (pin "14") (pinfunction "14_14") (pintype "bidirectional"))
    )
    (net (code "55") (name "/T11") (class "Default")
      (node (ref "R33") (pin "1") (pinfunction "1_1") (pintype "passive"))
      (node (ref "U9") (pin "12") (pinfunction "+IN_12") (pintype "input"))
      (node (ref "X2") (pin "15") (pinfunction "15_15") (pintype "bidirectional"))
    )
    (net (code "56") (name "/TXCAN_SLV") (class "Default")
      (node (ref "R56") (pin "1") (pinfunction "1_1") (pintype "passive"))
      (node (ref "U5") (pin "3") (pinfunction "TXD_3") (pintype "input"))
      (node (ref "U6") (pin "134") (pinfunction "PM3_134") (pintype "bidirectional"))
    )
    (net (code "57") (name "/{slash}SS1") (class "Default")
      (node (ref "R66") (pin "1") (pinfunction "1_1") (pintype "passive"))
      (node (ref "U3") (pin "CSBI") (pinfunction "CSBI_CSBI") (pintype "bidirectional"))
      (node (ref "U6") (pin "61") (pinfunction "PH3_61") (pintype "bidirectional"))
    )
    (net (code "58") (name "5V_BUS") (class "Default")
      (node (ref "C40") (pin "1") (pinfunction "1_1") (pintype "passive"))
      (node (ref "C7") (pin "1") (pinfunction "1_1") (pintype "passive"))
      (node (ref "R39") (pin "1") (pinfunction "1_1") (pintype "passive"))
      (node (ref "U5") (pin "8") (pinfunction "VCC2_8") (pintype "input"))
      (node (ref "X3") (pin "1") (pinfunction "1_1") (pintype "bidirectional"))
      (node (ref "X4") (pin "1") (pinfunction "1_1") (pintype "bidirectional"))
    )
    (net (code "59") (name "GND") (class "Default")
      (node (ref "C1") (pin "2") (pinfunction "2_2") (pintype "passive"))
      (node (ref "C10") (pin "2") (pinfunction "2_2") (pintype "passive"))
      (node (ref "C11") (pin "1") (pinfunction "1_1") (pintype "passive"))
      (node (ref "C12") (pin "2") (pinfunction "2_2") (pintype "passive"))
      (node (ref "C13") (pin "2") (pinfunction "2_2") (pintype "passive"))
      (node (ref "C14") (pin "2") (pinfunction "2_2") (pintype "passive"))
      (node (ref "C15") (pin "2") (pinfunction "2_2") (pintype "passive"))
      (node (ref "C16") (pin "2") (pinfunction "2_2") (pintype "passive"))
      (node (ref "C17") (pin "2") (pinfunction "2_2") (pintype "passive"))
      (node (ref "C18") (pin "2") (pinfunction "2_2") (pintype "passive"))
      (node (ref "C19") (pin "2") (pinfunction "2_2") (pintype "passive"))
      (node (ref "C2") (pin "2") (pinfunction "2_2") (pintype "passive"))
      (node (ref "C20") (pin "2") (pinfunction "2_2") (pintype "passive"))
      (node (ref "C21") (pin "2") (pinfunction "2_2") (pintype "passive"))
      (node (ref "C22") (pin "2") (pinfunction "2_2") (pintype "passive"))
      (node (ref "C23") (pin "2") (pinfunction "2_2") (pintype "passive"))
      (node (ref "C24") (pin "2") (pinfunction "2_2") (pintype "passive"))
      (node (ref "C25") (pin "2") (pinfunction "2_2") (pintype "passive"))
      (node (ref "C26") (pin "2") (pinfunction "2_2") (pintype "passive"))
      (node (ref "C27") (pin "2") (pinfunction "2_2") (pintype "passive"))
      (node (ref "C28") (pin "2") (pinfunction "2_2") (pintype "passive"))
      (node (ref "C29") (pin "2") (pinfunction "2_2") (pintype "passive"))
      (node (ref "C3") (pin "2") (pinfunction "2_2") (pintype "passive"))
      (node (ref "C31") (pin "2") (pinfunction "2_2") (pintype "passive"))
      (node (ref "C32") (pin "2") (pinfunction "2_2") (pintype "passive"))
      (node (ref "C34") (pin "1") (pinfunction "1_1") (pintype "passive"))
      (node (ref "C35") (pin "2") (pinfunction "2_2") (pintype "passive"))
      (node (ref "C36") (pin "1") (pinfunction "1_1") (pintype "passive"))
      (node (ref "C37") (pin "2") (pinfunction "2_2") (pintype "passive"))
      (node (ref "C38") (pin "1") (pinfunction "1_1") (pintype "passive"))
      (node (ref "C39") (pin "1") (pinfunction "1_1") (pintype "passive"))
      (node (ref "C41") (pin "2") (pinfunction "2_2") (pintype "passive"))
      (node (ref "C42") (pin "1") (pinfunction "1_1") (pintype "passive"))
      (node (ref "C43") (pin "C") (pinfunction "C_C") (pintype "bidirectional"))
      (node (ref "C5") (pin "2") (pinfunction "2_2") (pintype "passive"))
      (node (ref "C6") (pin "2") (pinfunction "2_2") (pintype "passive"))
      (node (ref "C9") (pin "1") (pinfunction "1_1") (pintype "passive"))
      (node (ref "D1") (pin "A") (pinfunction "A_A") (pintype "passive"))
      (node (ref "D13") (pin "A") (pinfunction "A_A") (pintype "passive"))
      (node (ref "D14") (pin "A") (pinfunction "A_A") (pintype "passive"))
      (node (ref "JP1") (pin "2") (pinfunction "2_2") (pintype "passive"))
      (node (ref "R21") (pin "2") (pinfunction "2_2") (pintype "passive"))
      (node (ref "R3") (pin "1") (pinfunction "1_1") (pintype "passive"))
      (node (ref "R38") (pin "1") (pinfunction "1_1") (pintype "passive"))
      (node (ref "R4") (pin "1") (pinfunction "1_1") (pintype "passive"))
      (node (ref "R49") (pin "1") (pinfunction "1_1") (pintype "passive"))
      (node (ref "R5") (pin "1") (pinfunction "1_1") (pintype "passive"))
      (node (ref "R50") (pin "1") (pinfunction "1_1") (pintype "passive"))
      (node (ref "R51") (pin "1") (pinfunction "1_1") (pintype "passive"))
      (node (ref "R52") (pin "1") (pinfunction "1_1") (pintype "passive"))
      (node (ref "R57") (pin "1") (pinfunction "1_1") (pintype "passive"))
      (node (ref "R58") (pin "1") (pinfunction "1_1") (pintype "passive"))
      (node (ref "R59") (pin "1") (pinfunction "1_1") (pintype "passive"))
      (node (ref "R60") (pin "1") (pinfunction "1_1") (pintype "passive"))
      (node (ref "R7") (pin "1") (pinfunction "1_1") (pintype "passive"))
      (node (ref "U1") (pin "11") (pinfunction "EP_11") (pintype "passive"))
      (node (ref "U1") (pin "9") (pinfunction "GND_9") (pintype "passive"))
      (node (ref "U11") (pin "2") (pinfunction "2_2") (pintype "bidirectional"))
      (node (ref "U11") (pin "5") (pinfunction "5_5") (pintype "bidirectional"))
      (node (ref "U3") (pin "A0") (pinfunction "A0_A0") (pintype "bidirectional"))
      (node (ref "U3") (pin "A1") (pinfunction "A1_A1") (pintype "bidirectional"))
      (node (ref "U3") (pin "A2") (pinfunction "A2_A2") (pintype "bidirectional"))
      (node (ref "U3") (pin "A3") (pinfunction "A3_A3") (pintype "bidirectional"))
      (node (ref "U3") (pin "C0") (pinfunction "C0_C0") (pintype "bidirectional"))
      (node (ref "U3") (pin "TOS") (pinfunction "TOS_TOS") (pintype "bidirectional"))
      (node (ref "U4") (pin "4") (pinfunction "GND_4") (pintype "passive"))
      (node (ref "U5") (pin "4") (pinfunction "GND1_4") (pintype "input"))
      (node (ref "U6") (pin "109") (pinfunction "VRL_109") (pintype "power_in"))
      (node (ref "U6") (pin "110") (pinfunction "VSSA*_110") (pintype "power_in"))
      (node (ref "U6") (pin "138") (pinfunction "VSSX1_138") (pintype "bidirectional"))
      (node (ref "U6") (pin "16") (pinfunction "VSS1_16") (pintype "power_in"))
      (node (ref "U6") (pin "27") (pinfunction "VSSX2*_27") (pintype "power_in"))
      (node (ref "U6") (pin "52") (pinfunction "VSSR1*_52") (pintype "power_in"))
      (node (ref "U6") (pin "57") (pinfunction "VSSPLL_57") (pintype "power_in"))
      (node (ref "U6") (pin "60") (pinfunction "TEST*_60") (pintype "power_in"))
      (node (ref "U6") (pin "81") (pinfunction "VSSR2*_81") (pintype "power_in"))
      (node (ref "U6") (pin "88") (pinfunction "VSS2_88") (pintype "power_in"))
      (node (ref "U7") (pin "11") (pinfunction "V-_11") (pintype "power_in"))
      (node (ref "U8") (pin "11") (pinfunction "V-_11") (pintype "power_in"))
      (node (ref "U9") (pin "11") (pinfunction "V-_11") (pintype "power_in"))
      (node (ref "X1") (pin "1") (pinfunction "1_1") (pintype "bidirectional"))
      (node (ref "X1") (pin "20") (pinfunction "20_20") (pintype "bidirectional"))
      (node (ref "X1") (pin "4") (pinfunction "4_4") (pintype "bidirectional"))
      (node (ref "X2") (pin "18") (pinfunction "18_18") (pintype "bidirectional"))
      (node (ref "X5") (pin "2") (pinfunction "GND_2") (pintype "bidirectional"))
    )
    (net (code "60") (name "GND_BUS") (class "Default")
      (node (ref "C40") (pin "2") (pinfunction "2_2") (pintype "passive"))
      (node (ref "C7") (pin "2") (pinfunction "2_2") (pintype "passive"))
      (node (ref "C8") (pin "2") (pinfunction "2_2") (pintype "passive"))
      (node (ref "U10") (pin "3") (pinfunction "3_3") (pintype "bidirectional"))
      (node (ref "U2") (pin "3") (pinfunction "3_3") (pintype "bidirectional"))
      (node (ref "U5") (pin "5") (pinfunction "GND2_5") (pintype "input"))
      (node (ref "X3") (pin "2") (pinfunction "2_2") (pintype "bidirectional"))
      (node (ref "X4") (pin "2") (pinfunction "2_2") (pintype "bidirectional"))
    )
    (net (code "61") (name "Net-(C1-Pad1)") (class "Default")
      (node (ref "C1") (pin "1") (pinfunction "1_1") (pintype "passive"))
      (node (ref "R1") (pin "1") (pinfunction "1_1") (pintype "passive"))
    )
    (net (code "62") (name "Net-(C8-Pad1)") (class "Default")
      (node (ref "C8") (pin "1") (pinfunction "1_1") (pintype "passive"))
      (node (ref "R40") (pin "2") (pinfunction "2_2") (pintype "passive"))
      (node (ref "R41") (pin "2") (pinfunction "2_2") (pintype "passive"))
    )
    (net (code "63") (name "Net-(C29-Pad1)") (class "Default")
      (node (ref "C29") (pin "1") (pinfunction "1_1") (pintype "passive"))
      (node (ref "R34") (pin "1") (pinfunction "1_1") (pintype "passive"))
      (node (ref "U3") (pin "V+") (pinfunction "V+_V+") (pintype "bidirectional"))
    )
    (net (code "64") (name "Net-(C31-Pad1)") (class "Default")
      (node (ref "C31") (pin "1") (pinfunction "1_1") (pintype "passive"))
      (node (ref "C33") (pin "2") (pinfunction "2_2") (pintype "passive"))
      (node (ref "U3") (pin "VREF") (pinfunction "VREF_VREF") (pintype "bidirectional"))
    )
    (net (code "65") (name "Net-(C32-Pad1)") (class "Default")
      (node (ref "C32") (pin "1") (pinfunction "1_1") (pintype "passive"))
      (node (ref "C33") (pin "1") (pinfunction "1_1") (pintype "passive"))
      (node (ref "R66") (pin "2") (pinfunction "2_2") (pintype "passive"))
      (node (ref "R67") (pin "2") (pinfunction "2_2") (pintype "passive"))
      (node (ref "R68") (pin "2") (pinfunction "2_2") (pintype "passive"))
      (node (ref "U3") (pin "VREG") (pinfunction "VREG_VREG") (pintype "bidirectional"))
    )
    (net (code "66") (name "Net-(LED1-PadC)") (class "Default")
      (node (ref "LED1") (pin "C") (pinfunction "C_C") (pintype "passive"))
      (node (ref "R38") (pin "2") (pinfunction "2_2") (pintype "passive"))
    )
    (net (code "67") (name "Net-(LED2-PadC)") (class "Default")
      (node (ref "LED2") (pin "C") (pinfunction "C_C") (pintype "passive"))
      (node (ref "R42") (pin "2") (pinfunction "2_2") (pintype "passive"))
    )
    (net (code "68") (name "Net-(LED3-PadC)") (class "Default")
      (node (ref "LED3") (pin "C") (pinfunction "C_C") (pintype "passive"))
      (node (ref "R43") (pin "2") (pinfunction "2_2") (pintype "passive"))
    )
    (net (code "69") (name "Net-(LED4-PadC)") (class "Default")
      (node (ref "LED4") (pin "C") (pinfunction "C_C") (pintype "passive"))
      (node (ref "R44") (pin "2") (pinfunction "2_2") (pintype "passive"))
    )
    (net (code "70") (name "Net-(R6-Pad1)") (class "Default")
      (node (ref "R6") (pin "1") (pinfunction "1_1") (pintype "passive"))
      (node (ref "R7") (pin "2") (pinfunction "2_2") (pintype "passive"))
      (node (ref "R8") (pin "2") (pinfunction "2_2") (pintype "passive"))
      (node (ref "U2") (pin "6") (pinfunction "6_6") (pintype "bidirectional"))
    )
    (net (code "71") (name "Net-(R21-Pad1)") (class "Default")
      (node (ref "R21") (pin "1") (pinfunction "1_1") (pintype "passive"))
      (node (ref "U3") (pin "NC") (pinfunction "NC_NC") (pintype "bidirectional"))
      (node (ref "U3") (pin "V-") (pinfunction "V-_V-") (pintype "bidirectional"))
    )
    (net (code "72") (name "Net-(R39-Pad2)") (class "Default")
      (node (ref "R39") (pin "2") (pinfunction "2_2") (pintype "passive"))
      (node (ref "U2") (pin "1") (pinfunction "1_1") (pintype "bidirectional"))
    )
    (net (code "73") (name "Net-(R45-Pad2)") (class "Default")
      (node (ref "R45") (pin "2") (pinfunction "2_2") (pintype "passive"))
      (node (ref "R57") (pin "2") (pinfunction "2_2") (pintype "passive"))
      (node (ref "R61") (pin "1") (pinfunction "1_1") (pintype "passive"))
      (node (ref "U11") (pin "4") (pinfunction "4_4") (pintype "bidirectional"))
      (node (ref "X6") (pin "1") (pinfunction "1_1") (pintype "passive"))
    )
    (net (code "74") (name "Net-(R46-Pad2)") (class "Default")
      (node (ref "R46") (pin "2") (pinfunction "2_2") (pintype "passive"))
      (node (ref "R58") (pin "2") (pinfunction "2_2") (pintype "passive"))
      (node (ref "R62") (pin "1") (pinfunction "1_1") (pintype "passive"))
      (node (ref "U11") (pin "6") (pinfunction "6_6") (pintype "bidirectional"))
      (node (ref "X6") (pin "2") (pinfunction "2_2") (pintype "passive"))
    )
    (net (code "75") (name "Net-(R47-Pad2)") (class "Default")
      (node (ref "R47") (pin "2") (pinfunction "2_2") (pintype "passive"))
      (node (ref "R59") (pin "2") (pinfunction "2_2") (pintype "passive"))
      (node (ref "R63") (pin "1") (pinfunction "1_1") (pintype "passive"))
      (node (ref "U11") (pin "1") (pinfunction "1_1") (pintype "bidirectional"))
      (node (ref "X6") (pin "3") (pinfunction "3_3") (pintype "passive"))
    )
    (net (code "76") (name "Net-(R48-Pad2)") (class "Default")
      (node (ref "R48") (pin "2") (pinfunction "2_2") (pintype "passive"))
      (node (ref "R60") (pin "2") (pinfunction "2_2") (pintype "passive"))
      (node (ref "R64") (pin "1") (pinfunction "1_1") (pintype "passive"))
      (node (ref "U11") (pin "3") (pinfunction "3_3") (pintype "bidirectional"))
      (node (ref "X6") (pin "4") (pinfunction "4_4") (pintype "passive"))
    )
    (net (code "77") (name "Net-(U1-BOOT)") (class "Default")
      (node (ref "C4") (pin "1") (pinfunction "1_1") (pintype "passive"))
      (node (ref "U1") (pin "1") (pinfunction "BOOT_1") (pintype "output"))
    )
    (net (code "78") (name "Net-(U1-COMP)") (class "Default")
      (node (ref "C2") (pin "1") (pinfunction "1_1") (pintype "passive"))
      (node (ref "R1") (pin "2") (pinfunction "2_2") (pintype "passive"))
      (node (ref "U1") (pin "8") (pinfunction "COMP_8") (pintype "output"))
    )
    (net (code "79") (name "Net-(U1-EN)") (class "Default")
      (node (ref "R5") (pin "2") (pinfunction "2_2") (pintype "passive"))
      (node (ref "R8") (pin "1") (pinfunction "1_1") (pintype "passive"))
      (node (ref "U1") (pin "3") (pinfunction "EN_3") (pintype "input"))
      (node (ref "U2") (pin "4") (pinfunction "4_4") (pintype "bidirectional"))
    )
    (net (code "80") (name "Net-(U1-PH)") (class "Default")
      (node (ref "C4") (pin "2") (pinfunction "2_2") (pintype "passive"))
      (node (ref "D1") (pin "C") (pinfunction "C_C") (pintype "passive"))
      (node (ref "L1") (pin "P$2") (pinfunction "P$2_P$2") (pintype "bidirectional"))
      (node (ref "U1") (pin "10") (pinfunction "PH_10") (pintype "input"))
    )
    (net (code "81") (name "Net-(U1-RT{slash}CLK)") (class "Default")
      (node (ref "R4") (pin "2") (pinfunction "2_2") (pintype "passive"))
      (node (ref "U1") (pin "5") (pinfunction "RT/CLK_5") (pintype "input"))
    )
    (net (code "82") (name "Net-(U1-SS{slash}TR)") (class "Default")
      (node (ref "C3") (pin "1") (pinfunction "1_1") (pintype "passive"))
      (node (ref "U1") (pin "4") (pinfunction "SS/TR_4") (pintype "input"))
    )
    (net (code "83") (name "Net-(U1-VSENSE)") (class "Default")
      (node (ref "R2") (pin "1") (pinfunction "1_1") (pintype "passive"))
      (node (ref "R3") (pin "2") (pinfunction "2_2") (pintype "passive"))
      (node (ref "U1") (pin "7") (pinfunction "VSENSE_7") (pintype "input"))
    )
    (net (code "84") (name "Net-(U4-1A)") (class "Default")
      (node (ref "R53") (pin "2") (pinfunction "2_2") (pintype "passive"))
      (node (ref "U4") (pin "1") (pinfunction "1A_1") (pintype "input"))
      (node (ref "U6") (pin "10") (pinfunction "PK0_10") (pintype "bidirectional"))
    )
    (net (code "85") (name "Net-(U4-1Y)") (class "Default")
      (node (ref "R44") (pin "1") (pinfunction "1_1") (pintype "passive"))
      (node (ref "U4") (pin "7") (pinfunction "1Y_7") (pintype "output"))
    )
    (net (code "86") (name "Net-(U4-2A)") (class "Default")
      (node (ref "R55") (pin "2") (pinfunction "2_2") (pintype "passive"))
      (node (ref "U4") (pin "3") (pinfunction "2A_3") (pintype "input"))
      (node (ref "U6") (pin "9") (pinfunction "PK1_9") (pintype "bidirectional"))
    )
    (net (code "87") (name "Net-(U4-2Y)") (class "Default")
      (node (ref "R43") (pin "1") (pinfunction "1_1") (pintype "passive"))
      (node (ref "U4") (pin "5") (pinfunction "2Y_5") (pintype "output"))
    )
    (net (code "88") (name "Net-(U4-3A)") (class "Default")
      (node (ref "R54") (pin "2") (pinfunction "2_2") (pintype "passive"))
      (node (ref "U4") (pin "6") (pinfunction "3A_6") (pintype "input"))
      (node (ref "U6") (pin "8") (pinfunction "PK2_8") (pintype "bidirectional"))
    )
    (net (code "89") (name "Net-(U4-3Y)") (class "Default")
      (node (ref "R42") (pin "1") (pinfunction "1_1") (pintype "passive"))
      (node (ref "U4") (pin "2") (pinfunction "3Y_2") (pintype "output"))
    )
    (net (code "90") (name "Net-(U6-EXTAL)") (class "Default")
      (node (ref "C27") (pin "1") (pinfunction "1_1") (pintype "passive"))
      (node (ref "U6") (pin "58") (pinfunction "EXTAL_58") (pintype "passive"))
      (node (ref "Y1") (pin "P$2") (pinfunction "2_P$2") (pintype "passive"))
    )
    (net (code "91") (name "Net-(U6-PD1)") (class "Default")
      (node (ref "R65") (pin "1") (pinfunction "1_1") (pintype "passive"))
      (node (ref "U6") (pin "66") (pinfunction "PD1_66") (pintype "bidirectional"))
      (node (ref "X1") (pin "17") (pinfunction "17_17") (pintype "bidirectional"))
    )
    (net (code "92") (name "Net-(U6-PJ4)") (class "Default")
      (node (ref "R45") (pin "1") (pinfunction "1_1") (pintype "passive"))
      (node (ref "U6") (pin "131") (pinfunction "PJ4_131") (pintype "bidirectional"))
    )
    (net (code "93") (name "Net-(U6-PJ5)") (class "Default")
      (node (ref "R46") (pin "1") (pinfunction "1_1") (pintype "passive"))
      (node (ref "U6") (pin "130") (pinfunction "PJ5_130") (pintype "bidirectional"))
    )
    (net (code "94") (name "Net-(U6-PJ6)") (class "Default")
      (node (ref "R47") (pin "1") (pinfunction "1_1") (pintype "passive"))
      (node (ref "U6") (pin "129") (pinfunction "PJ6_129") (pintype "bidirectional"))
    )
    (net (code "95") (name "Net-(U6-PJ7)") (class "Default")
      (node (ref "R48") (pin "1") (pinfunction "1_1") (pintype "passive"))
      (node (ref "U6") (pin "128") (pinfunction "PJ7_128") (pintype "bidirectional"))
    )
    (net (code "96") (name "Net-(U6-PS0)") (class "Default")
      (node (ref "R49") (pin "2") (pinfunction "2_2") (pintype "passive"))
      (node (ref "U6") (pin "119") (pinfunction "PS0_119") (pintype "bidirectional"))
    )
    (net (code "97") (name "Net-(U6-PS1)") (class "Default")
      (node (ref "R50") (pin "2") (pinfunction "2_2") (pintype "passive"))
      (node (ref "U6") (pin "120") (pinfunction "PS1_120") (pintype "bidirectional"))
    )
    (net (code "98") (name "Net-(U6-PS2)") (class "Default")
      (node (ref "R51") (pin "2") (pinfunction "2_2") (pintype "passive"))
      (node (ref "U6") (pin "121") (pinfunction "PS2_121") (pintype "bidirectional"))
    )
    (net (code "99") (name "Net-(U6-PS3)") (class "Default")
      (node (ref "R52") (pin "2") (pinfunction "2_2") (pintype "passive"))
      (node (ref "U6") (pin "122") (pinfunction "PS3_122") (pintype "bidirectional"))
    )
    (net (code "100") (name "Net-(U6-RESET)") (class "Default")
      (node (ref "C35") (pin "1") (pinfunction "1_1") (pintype "passive"))
      (node (ref "R37") (pin "1") (pinfunction "1_1") (pintype "passive"))
      (node (ref "U6") (pin "54") (pinfunction "RESET_54") (pintype "bidirectional"))
      (node (ref "X5") (pin "4") (pinfunction "~{RESET}_4") (pintype "bidirectional"))
    )
    (net (code "101") (name "Net-(U6-VDD1*)") (class "Default")
      (node (ref "C39") (pin "2") (pinfunction "2_2") (pintype "passive"))
      (node (ref "U6") (pin "15") (pinfunction "VDD1*_15") (pintype "power_in"))
    )
    (net (code "102") (name "Net-(U6-VDD2*)") (class "Default")
      (node (ref "C37") (pin "1") (pinfunction "1_1") (pintype "passive"))
      (node (ref "U6") (pin "87") (pinfunction "VDD2*_87") (pintype "power_in"))
    )
    (net (code "103") (name "Net-(U6-VDDPLL*)") (class "Default")
      (node (ref "C36") (pin "2") (pinfunction "2_2") (pintype "passive"))
      (node (ref "U6") (pin "55") (pinfunction "VDDPLL*_55") (pintype "power_in"))
      (node (ref "U6") (pin "56") (pinfunction "XFC*_56") (pintype "power_in"))
    )
    (net (code "104") (name "Net-(U6-XTAL)") (class "Default")
      (node (ref "C28") (pin "1") (pinfunction "1_1") (pintype "passive"))
      (node (ref "U6") (pin "59") (pinfunction "XTAL_59") (pintype "passive"))
      (node (ref "Y1") (pin "P$1") (pinfunction "1_P$1") (pintype "passive"))
    )
    (net (code "105") (name "V1") (class "Default")
      (node (ref "R20") (pin "1") (pinfunction "1_1") (pintype "passive"))
      (node (ref "X1") (pin "5") (pinfunction "5_5") (pintype "bidirectional"))
      (node (ref "X2") (pin "19") (pinfunction "19_19") (pintype "bidirectional"))
    )
    (net (code "106") (name "V2") (class "Default")
      (node (ref "R19") (pin "1") (pinfunction "1_1") (pintype "passive"))
      (node (ref "X1") (pin "6") (pinfunction "6_6") (pintype "bidirectional"))
      (node (ref "X2") (pin "20") (pinfunction "20_20") (pintype "bidirectional"))
    )
    (net (code "107") (name "V3") (class "Default")
      (node (ref "R18") (pin "1") (pinfunction "1_1") (pintype "passive"))
      (node (ref "X1") (pin "7") (pinfunction "7_7") (pintype "bidirectional"))
      (node (ref "X2") (pin "21") (pinfunction "21_21") (pintype "bidirectional"))
    )
    (net (code "108") (name "V4") (class "Default")
      (node (ref "R17") (pin "1") (pinfunction "1_1") (pintype "passive"))
      (node (ref "X1") (pin "8") (pinfunction "8_8") (pintype "bidirectional"))
      (node (ref "X2") (pin "22") (pinfunction "22_22") (pintype "bidirectional"))
    )
    (net (code "109") (name "V5") (class "Default")
      (node (ref "R16") (pin "1") (pinfunction "1_1") (pintype "passive"))
      (node (ref "X1") (pin "9") (pinfunction "9_9") (pintype "bidirectional"))
      (node (ref "X2") (pin "23") (pinfunction "23_23") (pintype "bidirectional"))
    )
    (net (code "110") (name "V6") (class "Default")
      (node (ref "R15") (pin "1") (pinfunction "1_1") (pintype "passive"))
      (node (ref "X1") (pin "10") (pinfunction "10_10") (pintype "bidirectional"))
      (node (ref "X2") (pin "24") (pinfunction "24_24") (pintype "bidirectional"))
    )
    (net (code "111") (name "V7") (class "Default")
      (node (ref "R14") (pin "1") (pinfunction "1_1") (pintype "passive"))
      (node (ref "X1") (pin "11") (pinfunction "11_11") (pintype "bidirectional"))
      (node (ref "X2") (pin "25") (pinfunction "25_25") (pintype "bidirectional"))
    )
    (net (code "112") (name "V8") (class "Default")
      (node (ref "R13") (pin "1") (pinfunction "1_1") (pintype "passive"))
      (node (ref "X1") (pin "12") (pinfunction "12_12") (pintype "bidirectional"))
      (node (ref "X2") (pin "26") (pinfunction "26_26") (pintype "bidirectional"))
    )
    (net (code "113") (name "V9") (class "Default")
      (node (ref "R12") (pin "1") (pinfunction "1_1") (pintype "passive"))
      (node (ref "X1") (pin "13") (pinfunction "13_13") (pintype "bidirectional"))
      (node (ref "X2") (pin "27") (pinfunction "27_27") (pintype "bidirectional"))
    )
    (net (code "114") (name "V10") (class "Default")
      (node (ref "R11") (pin "1") (pinfunction "1_1") (pintype "passive"))
      (node (ref "X1") (pin "14") (pinfunction "14_14") (pintype "bidirectional"))
      (node (ref "X2") (pin "28") (pinfunction "28_28") (pintype "bidirectional"))
    )
    (net (code "115") (name "V11") (class "Default")
      (node (ref "R10") (pin "1") (pinfunction "1_1") (pintype "passive"))
      (node (ref "X1") (pin "15") (pinfunction "15_15") (pintype "bidirectional"))
      (node (ref "X2") (pin "29") (pinfunction "29_29") (pintype "bidirectional"))
    )
    (net (code "116") (name "V12") (class "Default")
      (node (ref "FB") (pin "1") (pinfunction "1_1") (pintype "passive"))
      (node (ref "X1") (pin "16") (pinfunction "16_16") (pintype "bidirectional"))
      (node (ref "X2") (pin "30") (pinfunction "30_30") (pintype "bidirectional"))
    )
    (net (code "117") (name "V12_FERRITE") (class "Default")
      (node (ref "C5") (pin "1") (pinfunction "1_1") (pintype "passive"))
      (node (ref "C6") (pin "1") (pinfunction "1_1") (pintype "passive"))
      (node (ref "D14") (pin "C") (pinfunction "C_C") (pintype "passive"))
      (node (ref "FB") (pin "2") (pinfunction "2_2") (pintype "passive"))
      (node (ref "R34") (pin "2") (pinfunction "2_2") (pintype "passive"))
      (node (ref "R6") (pin "2") (pinfunction "2_2") (pintype "passive"))
      (node (ref "R9") (pin "1") (pinfunction "1_1") (pintype "passive"))
      (node (ref "U1") (pin "2") (pinfunction "VIN_2") (pintype "power_in"))
    )
    (net (code "118") (name "VCC") (class "Default")
      (node (ref "C10") (pin "1") (pinfunction "1_1") (pintype "passive"))
      (node (ref "C11") (pin "2") (pinfunction "2_2") (pintype "passive"))
      (node (ref "C12") (pin "1") (pinfunction "1_1") (pintype "passive"))
      (node (ref "C13") (pin "1") (pinfunction "1_1") (pintype "passive"))
      (node (ref "C14") (pin "1") (pinfunction "1_1") (pintype "passive"))
      (node (ref "C34") (pin "2") (pinfunction "2_2") (pintype "passive"))
      (node (ref "C38") (pin "2") (pinfunction "2_2") (pintype "passive"))
      (node (ref "C41") (pin "1") (pinfunction "1_1") (pintype "passive"))
      (node (ref "C42") (pin "2") (pinfunction "2_2") (pintype "passive"))
      (node (ref "C43") (pin "A") (pinfunction "A_A") (pintype "bidirectional"))
      (node (ref "C9") (pin "2") (pinfunction "2_2") (pintype "passive"))
      (node (ref "JP1") (pin "1") (pinfunction "1_1") (pintype "passive"))
      (node (ref "L1") (pin "P$1") (pinfunction "P$1_P$1") (pintype "bidirectional"))
      (node (ref "LED1") (pin "A") (pinfunction "A_A") (pintype "passive"))
      (node (ref "LED2") (pin "A") (pinfunction "A_A") (pintype "passive"))
      (node (ref "LED3") (pin "A") (pinfunction "A_A") (pintype "passive"))
      (node (ref "LED4") (pin "A") (pinfunction "A_A") (pintype "passive"))
      (node (ref "R2") (pin "2") (pinfunction "2_2") (pintype "passive"))
      (node (ref "R22") (pin "2") (pinfunction "2_2") (pintype "passive"))
      (node (ref "R23") (pin "2") (pinfunction "2_2") (pintype "passive"))
      (node (ref "R24") (pin "2") (pinfunction "2_2") (pintype "passive"))
      (node (ref "R25") (pin "2") (pinfunction "2_2") (pintype "passive"))
      (node (ref "R26") (pin "2") (pinfunction "2_2") (pintype "passive"))
      (node (ref "R27") (pin "2") (pinfunction "2_2") (pintype "passive"))
      (node (ref "R28") (pin "2") (pinfunction "2_2") (pintype "passive"))
      (node (ref "R29") (pin "2") (pinfunction "2_2") (pintype "passive"))
      (node (ref "R30") (pin "2") (pinfunction "2_2") (pintype "passive"))
      (node (ref "R31") (pin "2") (pinfunction "2_2") (pintype "passive"))
      (node (ref "R32") (pin "2") (pinfunction "2_2") (pintype "passive"))
      (node (ref "R33") (pin "2") (pinfunction "2_2") (pintype "passive"))
      (node (ref "R35") (pin "1") (pinfunction "1_1") (pintype "passive"))
      (node (ref "R37") (pin "2") (pinfunction "2_2") (pintype "passive"))
      (node (ref "R53") (pin "1") (pinfunction "1_1") (pintype "passive"))
      (node (ref "R54") (pin "1") (pinfunction "1_1") (pintype "passive"))
      (node (ref "R55") (pin "1") (pinfunction "1_1") (pintype "passive"))
      (node (ref "R56") (pin "2") (pinfunction "2_2") (pintype "passive"))
      (node (ref "R61") (pin "2") (pinfunction "2_2") (pintype "passive"))
      (node (ref "R62") (pin "2") (pinfunction "2_2") (pintype "passive"))
      (node (ref "R63") (pin "2") (pinfunction "2_2") (pintype "passive"))
      (node (ref "R64") (pin "2") (pinfunction "2_2") (pintype "passive"))
      (node (ref "R65") (pin "2") (pinfunction "2_2") (pintype "passive"))
      (node (ref "U4") (pin "8") (pinfunction "VCC_8") (pintype "power_in"))
      (node (ref "U5") (pin "1") (pinfunction "VCC1_1") (pintype "input"))
      (node (ref "U6") (pin "107") (pinfunction "VDDA*_107") (pintype "power_in"))
      (node (ref "U6") (pin "108") (pinfunction "VRH_108") (pintype "power_in"))
      (node (ref "U6") (pin "127") (pinfunction "VREGEN_127") (pintype "bidirectional"))
      (node (ref "U6") (pin "139") (pinfunction "VDDX1_139") (pintype "power_in"))
      (node (ref "U6") (pin "26") (pinfunction "VDDX2*_26") (pintype "power_in"))
      (node (ref "U6") (pin "53") (pinfunction "VDDR1*_53") (pintype "power_in"))
      (node (ref "U6") (pin "82") (pinfunction "VDDR2*_82") (pintype "power_in"))
      (node (ref "U7") (pin "4") (pinfunction "V+_4") (pintype "power_in"))
      (node (ref "U8") (pin "4") (pinfunction "V+_4") (pintype "power_in"))
      (node (ref "U9") (pin "4") (pinfunction "V+_4") (pintype "power_in"))
      (node (ref "X5") (pin "6") (pinfunction "VDD_6") (pintype "bidirectional"))
    )
    (net (code "119") (name "unconnected-(U1-PWRGD-Pad6)") (class "Default")
      (node (ref "U1") (pin "6") (pinfunction "PWRGD_6") (pintype "output"))
    )
    (net (code "120") (name "unconnected-(U3-PadGPIO1)") (class "Default")
      (node (ref "U3") (pin "GPIO1") (pinfunction "GPIO1_GPIO1") (pintype "bidirectional"))
    )
    (net (code "121") (name "unconnected-(U3-PadGPIO2)") (class "Default")
      (node (ref "U3") (pin "GPIO2") (pinfunction "GPIO2_GPIO2") (pintype "bidirectional"))
    )
    (net (code "122") (name "unconnected-(U3-PadVTEMP1)") (class "Default")
      (node (ref "U3") (pin "VTEMP1") (pinfunction "VTEMP1_VTEMP1") (pintype "bidirectional"))
    )
    (net (code "123") (name "unconnected-(U3-PadVTEMP2)") (class "Default")
      (node (ref "U3") (pin "VTEMP2") (pinfunction "VTEMP2_VTEMP2") (pintype "bidirectional"))
    )
    (net (code "124") (name "unconnected-(U3-PadWDTB)") (class "Default")
      (node (ref "U3") (pin "WDTB") (pinfunction "WDTB_WDTB") (pintype "bidirectional"))
    )
    (net (code "125") (name "unconnected-(U6-PA0-Pad73)") (class "Default")
      (node (ref "U6") (pin "73") (pinfunction "PA0_73") (pintype "bidirectional"))
    )
    (net (code "126") (name "unconnected-(U6-PA1-Pad74)") (class "Default")
      (node (ref "U6") (pin "74") (pinfunction "PA1_74") (pintype "bidirectional"))
    )
    (net (code "127") (name "unconnected-(U6-PA2-Pad75)") (class "Default")
      (node (ref "U6") (pin "75") (pinfunction "PA2_75") (pintype "bidirectional"))
    )
    (net (code "128") (name "unconnected-(U6-PA3-Pad76)") (class "Default")
      (node (ref "U6") (pin "76") (pinfunction "PA3_76") (pintype "bidirectional"))
    )
    (net (code "129") (name "unconnected-(U6-PA4-Pad77)") (class "Default")
      (node (ref "U6") (pin "77") (pinfunction "PA4_77") (pintype "bidirectional"))
    )
    (net (code "130") (name "unconnected-(U6-PA5-Pad78)") (class "Default")
      (node (ref "U6") (pin "78") (pinfunction "PA5_78") (pintype "bidirectional"))
    )
    (net (code "131") (name "unconnected-(U6-PA6-Pad79)") (class "Default")
      (node (ref "U6") (pin "79") (pinfunction "PA6_79") (pintype "bidirectional"))
    )
    (net (code "132") (name "unconnected-(U6-PA7-Pad80)") (class "Default")
      (node (ref "U6") (pin "80") (pinfunction "PA7_80") (pintype "bidirectional"))
    )
    (net (code "133") (name "unconnected-(U6-PAD12-AN12-Pad98)") (class "Default")
      (node (ref "U6") (pin "98") (pinfunction "PAD12-AN12_98") (pintype "bidirectional"))
    )
    (net (code "134") (name "unconnected-(U6-PAD13-AN13-Pad100)") (class "Default")
      (node (ref "U6") (pin "100") (pinfunction "PAD13-AN13_100") (pintype "bidirectional"))
    )
    (net (code "135") (name "unconnected-(U6-PAD14-AN14-Pad102)") (class "Default")
      (node (ref "U6") (pin "102") (pinfunction "PAD14-AN14_102") (pintype "bidirectional"))
    )
    (net (code "136") (name "unconnected-(U6-PAD15-AN15-Pad104)") (class "Default")
      (node (ref "U6") (pin "104") (pinfunction "PAD15-AN15_104") (pintype "bidirectional"))
    )
    (net (code "137") (name "unconnected-(U6-PAD16-AN16-Pad105)") (class "Default")
      (node (ref "U6") (pin "105") (pinfunction "PAD16-AN16_105") (pintype "bidirectional"))
    )
    (net (code "138") (name "unconnected-(U6-PAD17-AN17-Pad106)") (class "Default")
      (node (ref "U6") (pin "106") (pinfunction "PAD17-AN17_106") (pintype "bidirectional"))
    )
    (net (code "139") (name "unconnected-(U6-PAD18-Pad111)") (class "Default")
      (node (ref "U6") (pin "111") (pinfunction "PAD18_111") (pintype "bidirectional"))
    )
    (net (code "140") (name "unconnected-(U6-PAD19-Pad112)") (class "Default")
      (node (ref "U6") (pin "112") (pinfunction "PAD19_112") (pintype "bidirectional"))
    )
    (net (code "141") (name "unconnected-(U6-PAD20-Pad113)") (class "Default")
      (node (ref "U6") (pin "113") (pinfunction "PAD20_113") (pintype "bidirectional"))
    )
    (net (code "142") (name "unconnected-(U6-PAD21-Pad114)") (class "Default")
      (node (ref "U6") (pin "114") (pinfunction "PAD21_114") (pintype "bidirectional"))
    )
    (net (code "143") (name "unconnected-(U6-PAD22-Pad115)") (class "Default")
      (node (ref "U6") (pin "115") (pinfunction "PAD22_115") (pintype "bidirectional"))
    )
    (net (code "144") (name "unconnected-(U6-PAD23-Pad116)") (class "Default")
      (node (ref "U6") (pin "116") (pinfunction "PAD23_116") (pintype "bidirectional"))
    )
    (net (code "145") (name "unconnected-(U6-PB0-Pad32)") (class "Default")
      (node (ref "U6") (pin "32") (pinfunction "PB0_32") (pintype "bidirectional"))
    )
    (net (code "146") (name "unconnected-(U6-PB1-Pad33)") (class "Default")
      (node (ref "U6") (pin "33") (pinfunction "PB1_33") (pintype "bidirectional"))
    )
    (net (code "147") (name "unconnected-(U6-PB2-Pad34)") (class "Default")
      (node (ref "U6") (pin "34") (pinfunction "PB2_34") (pintype "bidirectional"))
    )
    (net (code "148") (name "unconnected-(U6-PB3-Pad35)") (class "Default")
      (node (ref "U6") (pin "35") (pinfunction "PB3_35") (pintype "bidirectional"))
    )
    (net (code "149") (name "unconnected-(U6-PB4-Pad36)") (class "Default")
      (node (ref "U6") (pin "36") (pinfunction "PB4_36") (pintype "bidirectional"))
    )
    (net (code "150") (name "unconnected-(U6-PB5-Pad37)") (class "Default")
      (node (ref "U6") (pin "37") (pinfunction "PB5_37") (pintype "bidirectional"))
    )
    (net (code "151") (name "unconnected-(U6-PB6-Pad38)") (class "Default")
      (node (ref "U6") (pin "38") (pinfunction "PB6_38") (pintype "bidirectional"))
    )
    (net (code "152") (name "unconnected-(U6-PB7-Pad39)") (class "Default")
      (node (ref "U6") (pin "39") (pinfunction "PB7_39") (pintype "bidirectional"))
    )
    (net (code "153") (name "unconnected-(U6-PC0-Pad28)") (class "Default")
      (node (ref "U6") (pin "28") (pinfunction "PC0_28") (pintype "bidirectional"))
    )
    (net (code "154") (name "unconnected-(U6-PC1-Pad29)") (class "Default")
      (node (ref "U6") (pin "29") (pinfunction "PC1_29") (pintype "bidirectional"))
    )
    (net (code "155") (name "unconnected-(U6-PC2-Pad30)") (class "Default")
      (node (ref "U6") (pin "30") (pinfunction "PC2_30") (pintype "bidirectional"))
    )
    (net (code "156") (name "unconnected-(U6-PC3-Pad31)") (class "Default")
      (node (ref "U6") (pin "31") (pinfunction "PC3_31") (pintype "bidirectional"))
    )
    (net (code "157") (name "unconnected-(U6-PC4-Pad40)") (class "Default")
      (node (ref "U6") (pin "40") (pinfunction "PC4_40") (pintype "bidirectional"))
    )
    (net (code "158") (name "unconnected-(U6-PC5-Pad41)") (class "Default")
      (node (ref "U6") (pin "41") (pinfunction "PC5_41") (pintype "bidirectional"))
    )
    (net (code "159") (name "unconnected-(U6-PC6-Pad42)") (class "Default")
      (node (ref "U6") (pin "42") (pinfunction "PC6_42") (pintype "bidirectional"))
    )
    (net (code "160") (name "unconnected-(U6-PC7-Pad43)") (class "Default")
      (node (ref "U6") (pin "43") (pinfunction "PC7_43") (pintype "bidirectional"))
    )
    (net (code "161") (name "unconnected-(U6-PD0-Pad65)") (class "Default")
      (node (ref "U6") (pin "65") (pinfunction "PD0_65") (pintype "bidirectional"))
    )
    (net (code "162") (name "unconnected-(U6-PD2-Pad67)") (class "Default")
      (node (ref "U6") (pin "67") (pinfunction "PD2_67") (pintype "bidirectional"))
    )
    (net (code "163") (name "unconnected-(U6-PD3-Pad68)") (class "Default")
      (node (ref "U6") (pin "68") (pinfunction "PD3_68") (pintype "bidirectional"))
    )
    (net (code "164") (name "unconnected-(U6-PD4-DATA4-Pad83)") (class "Default")
      (node (ref "U6") (pin "83") (pinfunction "PD4-DATA4_83") (pintype "bidirectional"))
    )
    (net (code "165") (name "unconnected-(U6-PD5-DATA5-Pad84)") (class "Default")
      (node (ref "U6") (pin "84") (pinfunction "PD5-DATA5_84") (pintype "bidirectional"))
    )
    (net (code "166") (name "unconnected-(U6-PD6-DATA6-Pad85)") (class "Default")
      (node (ref "U6") (pin "85") (pinfunction "PD6-DATA6_85") (pintype "bidirectional"))
    )
    (net (code "167") (name "unconnected-(U6-PD7-DATA7-Pad86)") (class "Default")
      (node (ref "U6") (pin "86") (pinfunction "PD7-DATA7_86") (pintype "bidirectional"))
    )
    (net (code "168") (name "unconnected-(U6-PE0-XIRQ-Pad72)") (class "Default")
      (node (ref "U6") (pin "72") (pinfunction "PE0-XIRQ_72") (pintype "input"))
    )
    (net (code "169") (name "unconnected-(U6-PE1-IRQ-Pad71)") (class "Default")
      (node (ref "U6") (pin "71") (pinfunction "PE1-IRQ_71") (pintype "input"))
    )
    (net (code "170") (name "unconnected-(U6-PE2-Pad70)") (class "Default")
      (node (ref "U6") (pin "70") (pinfunction "PE2_70") (pintype "bidirectional"))
    )
    (net (code "171") (name "unconnected-(U6-PE3-Pad69)") (class "Default")
      (node (ref "U6") (pin "69") (pinfunction "PE3_69") (pintype "bidirectional"))
    )
    (net (code "172") (name "unconnected-(U6-PE4-Pad51)") (class "Default")
      (node (ref "U6") (pin "51") (pinfunction "PE4_51") (pintype "bidirectional"))
    )
    (net (code "173") (name "unconnected-(U6-PE5-Pad50)") (class "Default")
      (node (ref "U6") (pin "50") (pinfunction "PE5_50") (pintype "bidirectional"))
    )
    (net (code "174") (name "unconnected-(U6-PE6-Pad49)") (class "Default")
      (node (ref "U6") (pin "49") (pinfunction "PE6_49") (pintype "bidirectional"))
    )
    (net (code "175") (name "unconnected-(U6-PE7-Pad48)") (class "Default")
      (node (ref "U6") (pin "48") (pinfunction "PE7_48") (pintype "bidirectional"))
    )
    (net (code "176") (name "unconnected-(U6-PH4-Pad47)") (class "Default")
      (node (ref "U6") (pin "47") (pinfunction "PH4_47") (pintype "bidirectional"))
    )
    (net (code "177") (name "unconnected-(U6-PH5-Pad46)") (class "Default")
      (node (ref "U6") (pin "46") (pinfunction "PH5_46") (pintype "bidirectional"))
    )
    (net (code "178") (name "unconnected-(U6-PH6-Pad45)") (class "Default")
      (node (ref "U6") (pin "45") (pinfunction "PH6_45") (pintype "bidirectional"))
    )
    (net (code "179") (name "unconnected-(U6-PH7-Pad44)") (class "Default")
      (node (ref "U6") (pin "44") (pinfunction "PH7_44") (pintype "bidirectional"))
    )
    (net (code "180") (name "unconnected-(U6-PJ0-Pad24)") (class "Default")
      (node (ref "U6") (pin "24") (pinfunction "PJ0_24") (pintype "bidirectional"))
    )
    (net (code "181") (name "unconnected-(U6-PJ1-Pad23)") (class "Default")
      (node (ref "U6") (pin "23") (pinfunction "PJ1_23") (pintype "bidirectional"))
    )
    (net (code "182") (name "unconnected-(U6-PJ2-Pad5)") (class "Default")
      (node (ref "U6") (pin "5") (pinfunction "PJ2_5") (pintype "bidirectional"))
    )
    (net (code "183") (name "unconnected-(U6-PK3-Pad7)") (class "Default")
      (node (ref "U6") (pin "7") (pinfunction "PK3_7") (pintype "bidirectional"))
    )
    (net (code "184") (name "unconnected-(U6-PK4-Pad22)") (class "Default")
      (node (ref "U6") (pin "22") (pinfunction "PK4_22") (pintype "bidirectional"))
    )
    (net (code "185") (name "unconnected-(U6-PK5-Pad21)") (class "Default")
      (node (ref "U6") (pin "21") (pinfunction "PK5_21") (pintype "bidirectional"))
    )
    (net (code "186") (name "unconnected-(U6-PK6-Pad6)") (class "Default")
      (node (ref "U6") (pin "6") (pinfunction "PK6_6") (pintype "bidirectional"))
    )
    (net (code "187") (name "unconnected-(U6-PK7-Pad140)") (class "Default")
      (node (ref "U6") (pin "140") (pinfunction "PK7_140") (pintype "bidirectional"))
    )
    (net (code "188") (name "unconnected-(U6-PM0-Pad137)") (class "Default")
      (node (ref "U6") (pin "137") (pinfunction "PM0_137") (pintype "bidirectional"))
    )
    (net (code "189") (name "unconnected-(U6-PM1-Pad136)") (class "Default")
      (node (ref "U6") (pin "136") (pinfunction "PM1_136") (pintype "bidirectional"))
    )
    (net (code "190") (name "unconnected-(U6-PM4-Pad133)") (class "Default")
      (node (ref "U6") (pin "133") (pinfunction "PM4_133") (pintype "bidirectional"))
    )
    (net (code "191") (name "unconnected-(U6-PM5-Pad132)") (class "Default")
      (node (ref "U6") (pin "132") (pinfunction "PM5_132") (pintype "bidirectional"))
    )
    (net (code "192") (name "unconnected-(U6-PM6-Pad118)") (class "Default")
      (node (ref "U6") (pin "118") (pinfunction "PM6_118") (pintype "bidirectional"))
    )
    (net (code "193") (name "unconnected-(U6-PM7-Pad117)") (class "Default")
      (node (ref "U6") (pin "117") (pinfunction "PM7_117") (pintype "bidirectional"))
    )
    (net (code "194") (name "unconnected-(U6-PP0-Pad4)") (class "Default")
      (node (ref "U6") (pin "4") (pinfunction "PP0_4") (pintype "bidirectional"))
    )
    (net (code "195") (name "unconnected-(U6-PP1-Pad3)") (class "Default")
      (node (ref "U6") (pin "3") (pinfunction "PP1_3") (pintype "bidirectional"))
    )
    (net (code "196") (name "unconnected-(U6-PP2-Pad2)") (class "Default")
      (node (ref "U6") (pin "2") (pinfunction "PP2_2") (pintype "bidirectional"))
    )
    (net (code "197") (name "unconnected-(U6-PP3-Pad1)") (class "Default")
      (node (ref "U6") (pin "1") (pinfunction "PP3_1") (pintype "bidirectional"))
    )
    (net (code "198") (name "unconnected-(U6-PP4-Pad144)") (class "Default")
      (node (ref "U6") (pin "144") (pinfunction "PP4_144") (pintype "bidirectional"))
    )
    (net (code "199") (name "unconnected-(U6-PP5-Pad143)") (class "Default")
      (node (ref "U6") (pin "143") (pinfunction "PP5_143") (pintype "bidirectional"))
    )
    (net (code "200") (name "unconnected-(U6-PP6-Pad142)") (class "Default")
      (node (ref "U6") (pin "142") (pinfunction "PP6_142") (pintype "bidirectional"))
    )
    (net (code "201") (name "unconnected-(U6-PP7-Pad141)") (class "Default")
      (node (ref "U6") (pin "141") (pinfunction "PP7_141") (pintype "bidirectional"))
    )
    (net (code "202") (name "unconnected-(U6-PS4-Pad123)") (class "Default")
      (node (ref "U6") (pin "123") (pinfunction "PS4_123") (pintype "bidirectional"))
    )
    (net (code "203") (name "unconnected-(U6-PS5-Pad124)") (class "Default")
      (node (ref "U6") (pin "124") (pinfunction "PS5_124") (pintype "bidirectional"))
    )
    (net (code "204") (name "unconnected-(U6-PS6-Pad125)") (class "Default")
      (node (ref "U6") (pin "125") (pinfunction "PS6_125") (pintype "bidirectional"))
    )
    (net (code "205") (name "unconnected-(U6-PS7-Pad126)") (class "Default")
      (node (ref "U6") (pin "126") (pinfunction "PS7_126") (pintype "bidirectional"))
    )
    (net (code "206") (name "unconnected-(U6-PT0-Pad11)") (class "Default")
      (node (ref "U6") (pin "11") (pinfunction "PT0_11") (pintype "bidirectional"))
    )
    (net (code "207") (name "unconnected-(U6-PT1-Pad12)") (class "Default")
      (node (ref "U6") (pin "12") (pinfunction "PT1_12") (pintype "bidirectional"))
    )
    (net (code "208") (name "unconnected-(U6-PT2-Pad13)") (class "Default")
      (node (ref "U6") (pin "13") (pinfunction "PT2_13") (pintype "bidirectional"))
    )
    (net (code "209") (name "unconnected-(U6-PT3-Pad14)") (class "Default")
      (node (ref "U6") (pin "14") (pinfunction "PT3_14") (pintype "bidirectional"))
    )
    (net (code "210") (name "unconnected-(U6-PT4-Pad17)") (class "Default")
      (node (ref "U6") (pin "17") (pinfunction "PT4_17") (pintype "bidirectional"))
    )
    (net (code "211") (name "unconnected-(U6-PT5-Pad18)") (class "Default")
      (node (ref "U6") (pin "18") (pinfunction "PT5_18") (pintype "bidirectional"))
    )
    (net (code "212") (name "unconnected-(U6-PT6-Pad19)") (class "Default")
      (node (ref "U6") (pin "19") (pinfunction "PT6_19") (pintype "bidirectional"))
    )
    (net (code "213") (name "unconnected-(U6-PT7-Pad20)") (class "Default")
      (node (ref "U6") (pin "20") (pinfunction "PT7_20") (pintype "bidirectional"))
    )
    (net (code "214") (name "unconnected-(X1-Pad2)") (class "Default")
      (node (ref "X1") (pin "2") (pinfunction "2_2") (pintype "bidirectional"))
    )
    (net (code "215") (name "unconnected-(X1-Pad3)") (class "Default")
      (node (ref "X1") (pin "3") (pinfunction "3_3") (pintype "bidirectional"))
    )
    (net (code "216") (name "unconnected-(X1-Pad18)") (class "Default")
      (node (ref "X1") (pin "18") (pinfunction "18_18") (pintype "bidirectional"))
    )
    (net (code "217") (name "unconnected-(X1-Pad19)") (class "Default")
      (node (ref "X1") (pin "19") (pinfunction "19_19") (pintype "bidirectional"))
    )
    (net (code "218") (name "unconnected-(X2-Pad1)") (class "Default")
      (node (ref "X2") (pin "1") (pinfunction "1_1") (pintype "bidirectional"))
    )
    (net (code "219") (name "unconnected-(X2-Pad2)") (class "Default")
      (node (ref "X2") (pin "2") (pinfunction "2_2") (pintype "bidirectional"))
    )
    (net (code "220") (name "unconnected-(X2-Pad3)") (class "Default")
      (node (ref "X2") (pin "3") (pinfunction "3_3") (pintype "bidirectional"))
    )
    (net (code "221") (name "unconnected-(X2-Pad16)") (class "Default")
      (node (ref "X2") (pin "16") (pinfunction "16_16") (pintype "bidirectional"))
    )
    (net (code "222") (name "unconnected-(X2-Pad17)") (class "Default")
      (node (ref "X2") (pin "17") (pinfunction "17_17") (pintype "bidirectional"))
    )
    (net (code "223") (name "unconnected-(X5-NC-Pad3)") (class "Default")
      (node (ref "X5") (pin "3") (pinfunction "NC_3") (pintype "bidirectional"))
    )
    (net (code "224") (name "unconnected-(X5-VPP-Pad5)") (class "Default")
      (node (ref "X5") (pin "5") (pinfunction "VPP_5") (pintype "bidirectional"))
    )
  )
)
